# OBCv4_21.net
KiCad netlist of a schematic drawn in EAGLE
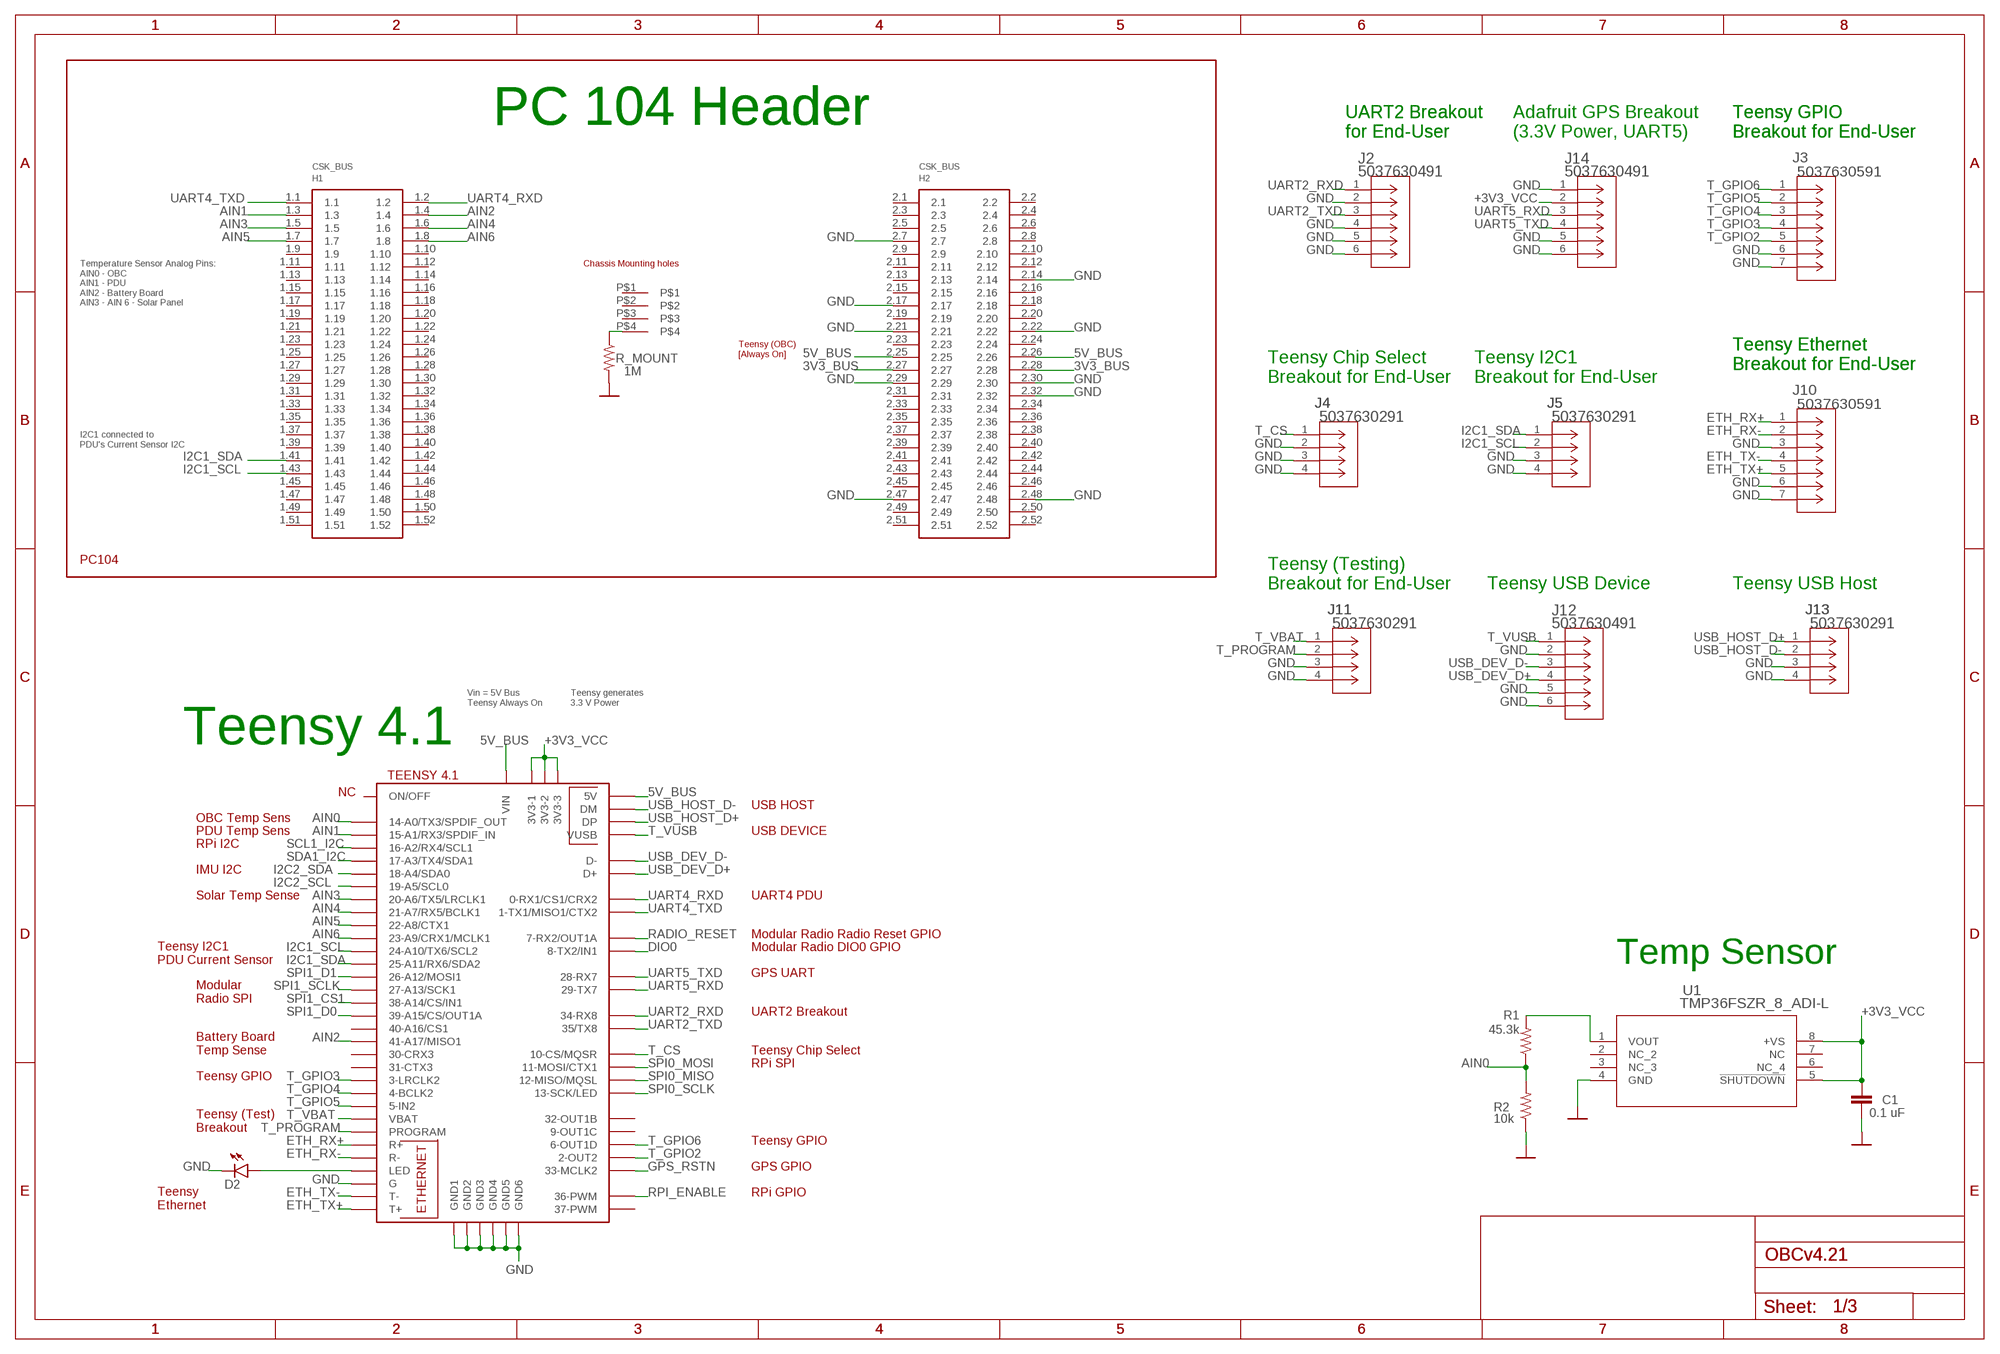
[diagram p0: schematic, sheet 1]
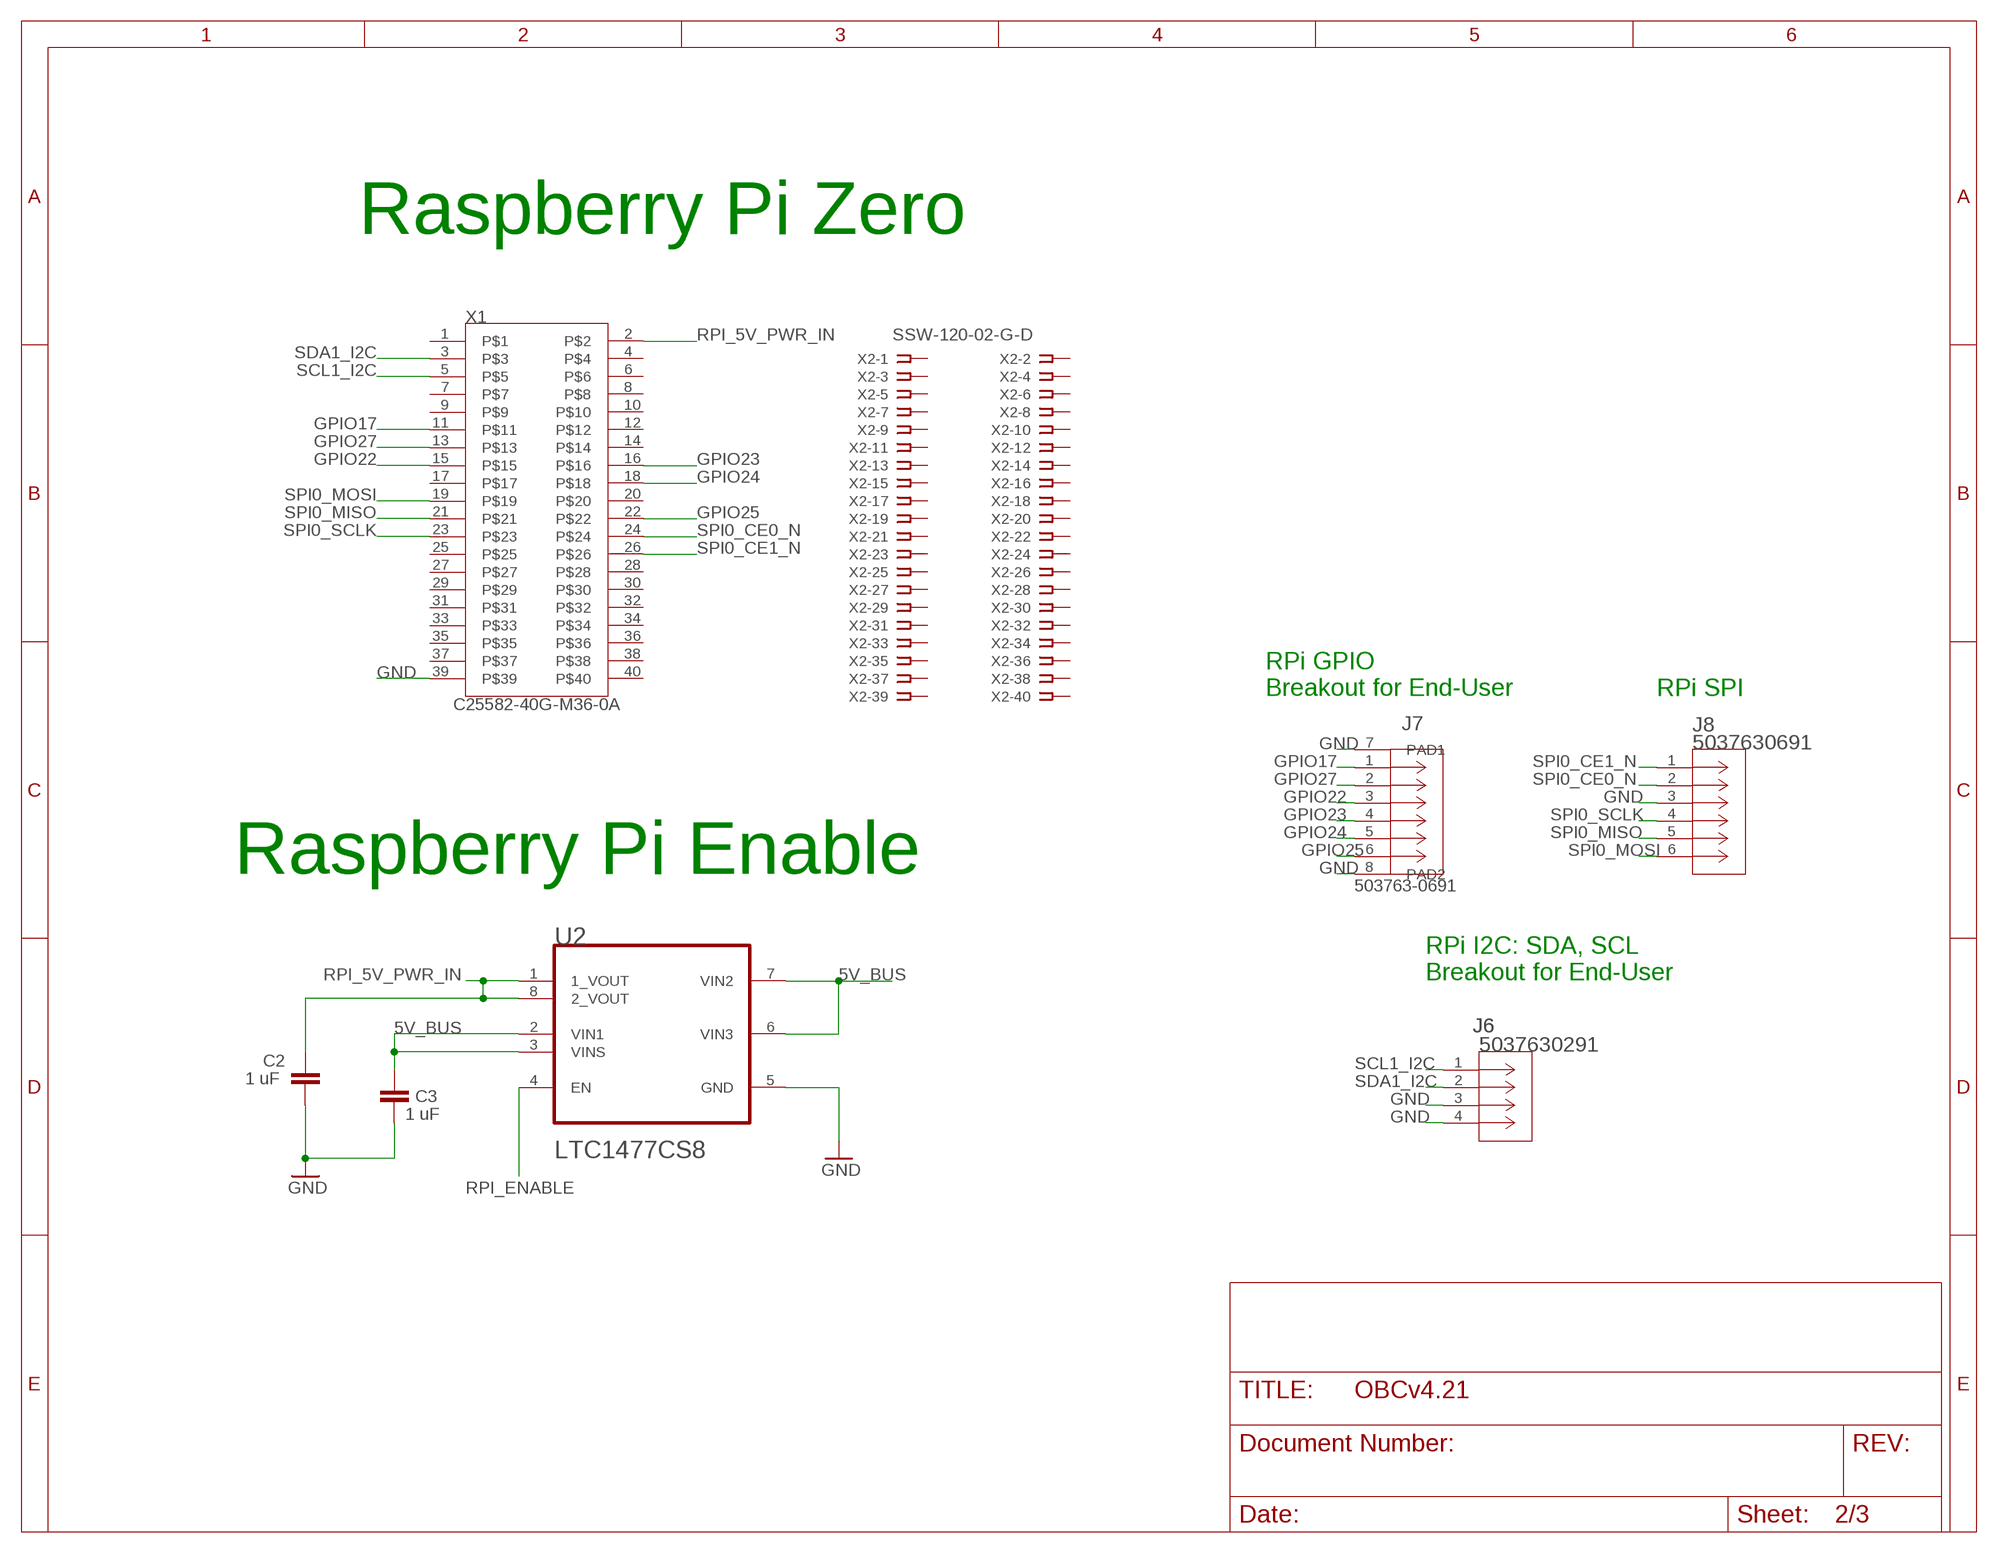
[diagram p1: schematic, sheet 2]
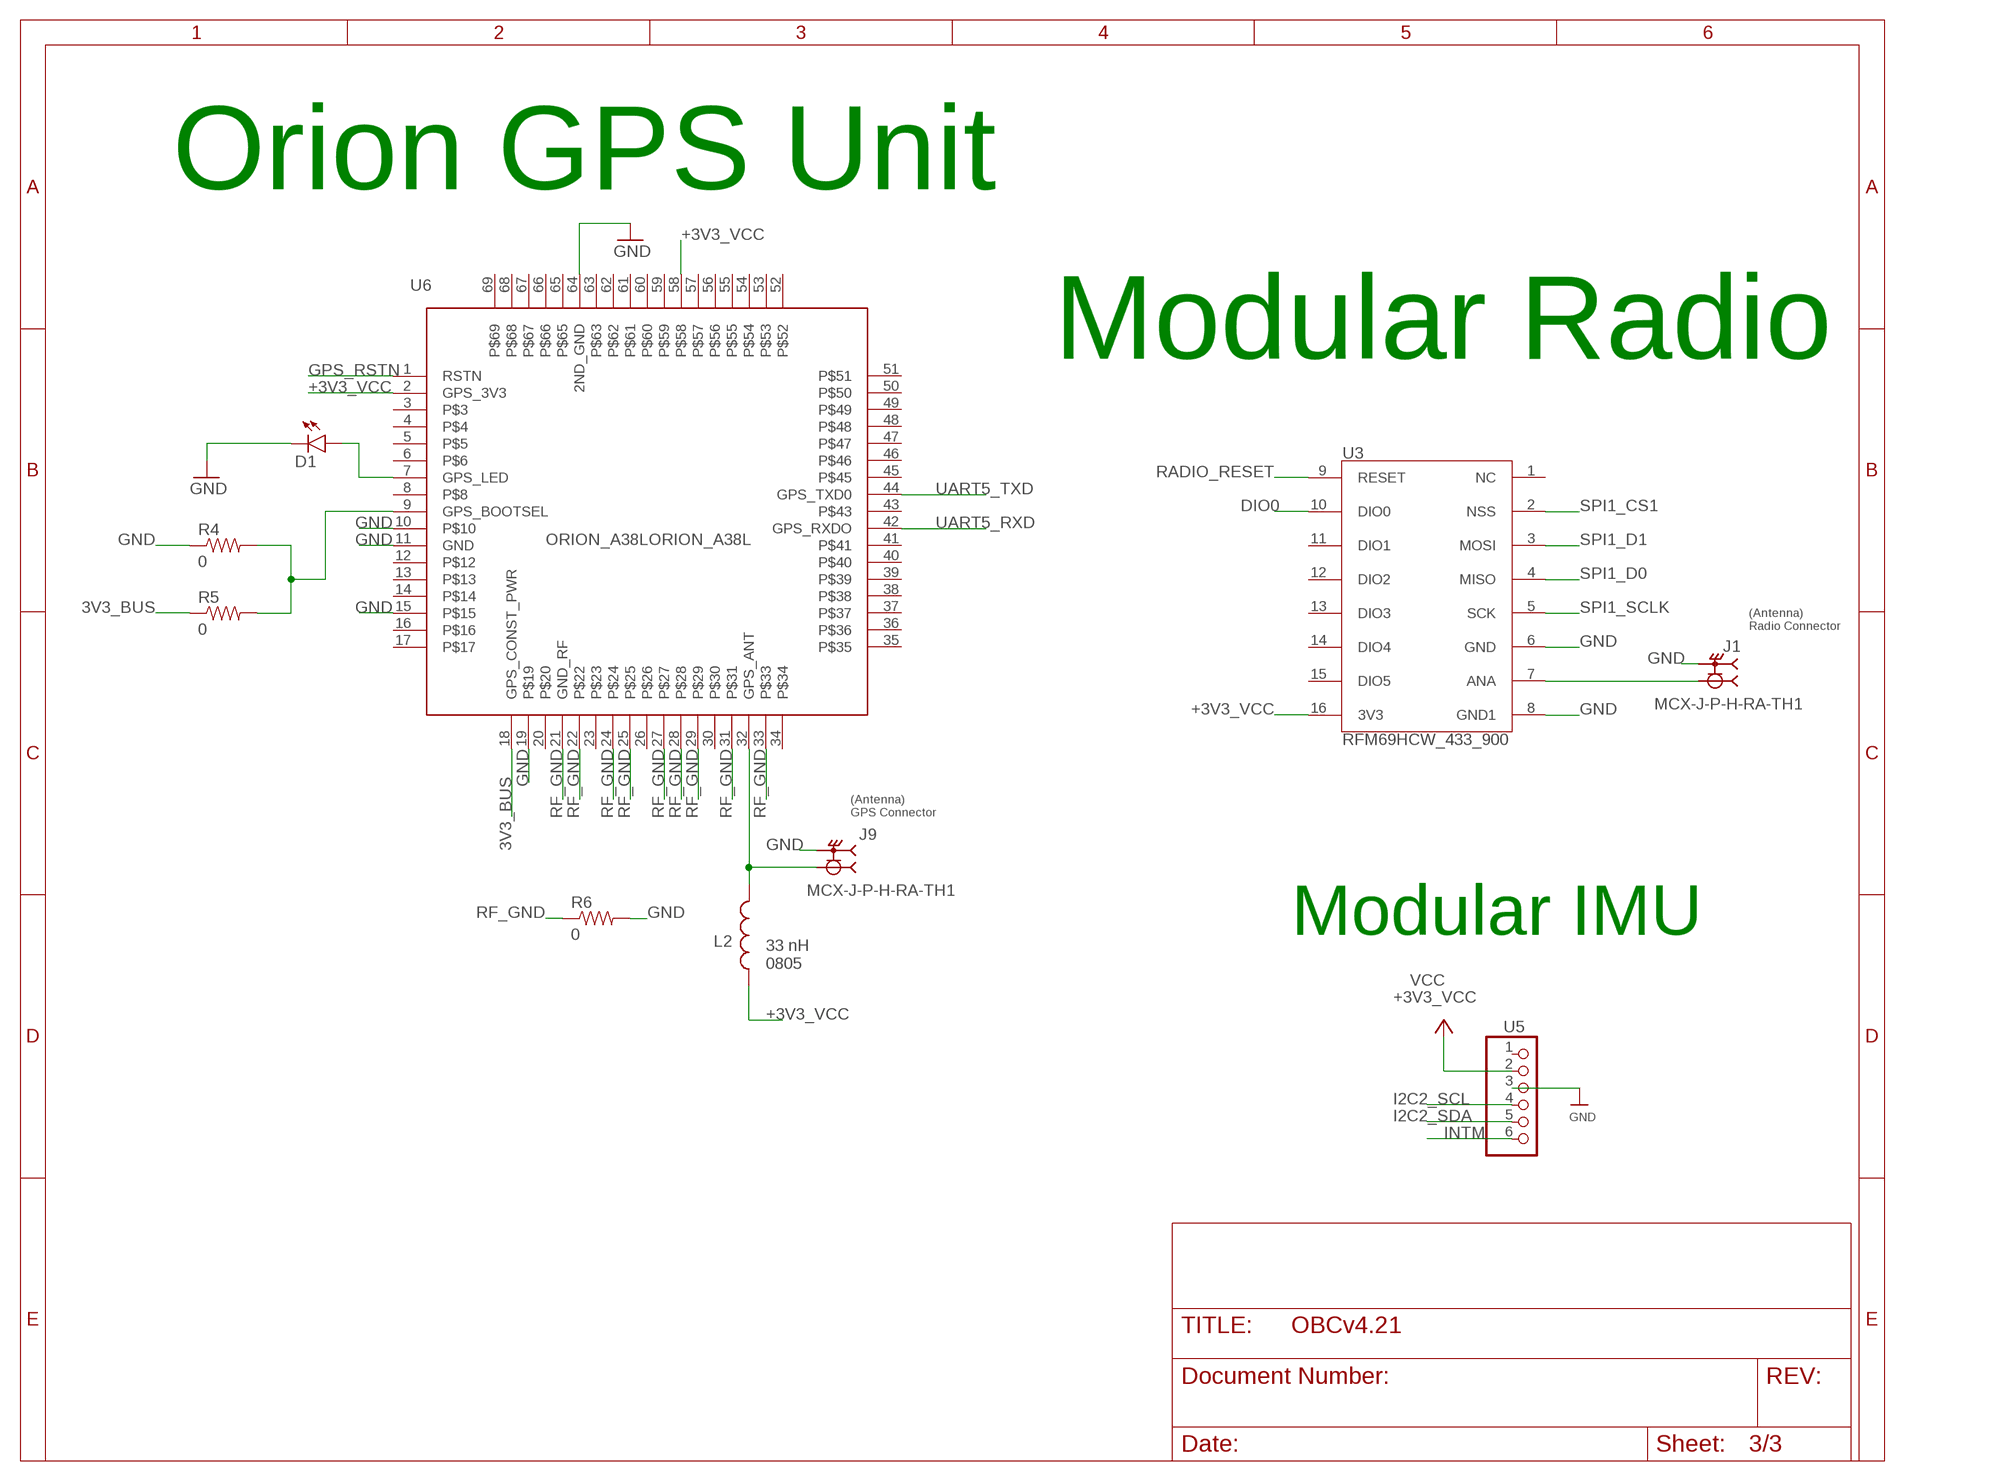
[diagram p2: schematic, sheet 3]

(export (version "E")
  (design (tool "Eeschema 10.0.6"))
  (components
    (comp (ref "C2")
      (value "1 uF")
      (footprint "eagle-import:0805")
      (libsource (lib "eagle-import") (part "CAP0805"))
    )
    (comp (ref "C3")
      (value "1 uF")
      (footprint "eagle-import:0805")
      (libsource (lib "eagle-import") (part "CAP0805"))
    )
    (comp (ref "J6")
      (value "5037630291")
      (footprint "eagle-import:CON_5037630291")
      (fields (field (name "COPYRIGHT") "Copyright (C) 2018 Accelerated Designs. All rights reserved"))
      (libsource (lib "eagle-import") (part "5037630291"))
    )
    (comp (ref "J7")
      (value "503763-0691")
      (footprint "eagle-import:CONN_503763-0691_MOL")
      (fields (field (name "COPYRIGHT") "Copyright (C) 2018 Accelerated Designs. All rights reserved"))
      (libsource (lib "eagle-import") (part "503763-0691"))
    )
    (comp (ref "J8")
      (value "5037630691")
      (footprint "eagle-import:CONN_503763-0691_MOL")
      (fields
        (field (name "MANUFACTURER_PART_NUMBER") "503763-0691")
        (field (name "COPYRIGHT") "Copyright (C) 2018 Accelerated Designs. All rights reserved")
      )
      (libsource (lib "eagle-import") (part "5037630691"))
    )
    (comp (ref "U2")
      (value "LTC1477CS8LINEAR_TECHNOLOGY_LTC1477CS8_0_2")
      (footprint "eagle-import:LINEAR_TECHNOLOGY_LTC1477CS8_2")
      (fields (field (name "MF") "Linear Technology") (field (name "MPN") "LTC1477CS8"))
      (libsource (lib "eagle-import") (part "LTC1477CS8LINEAR_TECHNOLOGY_LTC1477CS8_0_2"))
    )
    (comp (ref "X1")
      (value "C25582-40G-M36-0A")
      (footprint "eagle-import:ADAFRUIT_C25582-40G-M36-0A_0")
      (libsource (lib "eagle-import") (part "C25582-40G-M36-0A"))
    )
    (comp (ref "X2")
      (value "SSW-120-02-G-D")
      (footprint "eagle-import:SSW-120-02-G-D")
      (fields (field (name "MF") "Samtec Inc."))
      (libsource (lib "eagle-import") (part "SSW-120-02-G-D"))
    )
    (comp (ref "C1")
      (value "0.1 uF")
      (footprint "eagle-import:0805")
      (libsource (lib "eagle-import") (part "CAP0805"))
    )
    (comp (ref "D2")
      (value "LEDCHIP-LED0603")
      (footprint "eagle-import:CHIP-LED0603")
      (libsource (lib "eagle-import") (part "LEDCHIP-LED0603"))
    )
    (comp (ref "H1")
      (value "PC104_WCONN")
      (footprint "eagle-import:PC104_WCONN")
      (libsource (lib "eagle-import") (part "PC104_WCONN"))
    )
    (comp (ref "J2")
      (value "5037630491")
      (footprint "eagle-import:CON_5037630491")
      (fields (field (name "COPYRIGHT") "Copyright (C) 2018 Accelerated Designs. All rights reserved"))
      (libsource (lib "eagle-import") (part "5037630491"))
    )
    (comp (ref "J3")
      (value "5037630591")
      (footprint "eagle-import:CON_5037630591")
      (fields (field (name "COPYRIGHT") "Copyright (C) 2021 Ultra Librarian. All rights reserved."))
      (libsource (lib "eagle-import") (part "5037630591"))
    )
    (comp (ref "J4")
      (value "5037630291")
      (footprint "eagle-import:CON_5037630291")
      (fields (field (name "COPYRIGHT") "Copyright (C) 2018 Accelerated Designs. All rights reserved"))
      (libsource (lib "eagle-import") (part "5037630291"))
    )
    (comp (ref "J5")
      (value "5037630291")
      (footprint "eagle-import:CON_5037630291")
      (fields (field (name "COPYRIGHT") "Copyright (C) 2018 Accelerated Designs. All rights reserved"))
      (libsource (lib "eagle-import") (part "5037630291"))
    )
    (comp (ref "J10")
      (value "5037630591")
      (footprint "eagle-import:CON_5037630591")
      (fields (field (name "COPYRIGHT") "Copyright (C) 2021 Ultra Librarian. All rights reserved."))
      (libsource (lib "eagle-import") (part "5037630591"))
    )
    (comp (ref "J11")
      (value "5037630291")
      (footprint "eagle-import:CON_5037630291")
      (fields (field (name "COPYRIGHT") "Copyright (C) 2018 Accelerated Designs. All rights reserved"))
      (libsource (lib "eagle-import") (part "5037630291"))
    )
    (comp (ref "J12")
      (value "5037630491")
      (footprint "eagle-import:CON_5037630491")
      (fields (field (name "COPYRIGHT") "Copyright (C) 2018 Accelerated Designs. All rights reserved"))
      (libsource (lib "eagle-import") (part "5037630491"))
    )
    (comp (ref "J13")
      (value "5037630291")
      (footprint "eagle-import:CON_5037630291")
      (fields (field (name "COPYRIGHT") "Copyright (C) 2018 Accelerated Designs. All rights reserved"))
      (libsource (lib "eagle-import") (part "5037630291"))
    )
    (comp (ref "J14")
      (value "5037630491")
      (footprint "eagle-import:CON_5037630491")
      (fields (field (name "COPYRIGHT") "Copyright (C) 2018 Accelerated Designs. All rights reserved"))
      (libsource (lib "eagle-import") (part "5037630491"))
    )
    (comp (ref "R1")
      (value "45.3k")
      (footprint "eagle-import:0805")
      (libsource (lib "eagle-import") (part "RESISTOR0805-RES"))
    )
    (comp (ref "R2")
      (value "10k")
      (footprint "eagle-import:0805")
      (libsource (lib "eagle-import") (part "RESISTOR0805-RES"))
    )
    (comp (ref "R_MOUNT")
      (value "1M")
      (footprint "eagle-import:0805")
      (libsource (lib "eagle-import") (part "RESISTOR0805-RES"))
    )
    (comp (ref "U$1")
      (value "TEENSY41")
      (footprint "eagle-import:TEENSY41")
      (libsource (lib "eagle-import") (part "TEENSY41"))
    )
    (comp (ref "U1")
      (value "TMP36FSZR_8_ADI-L")
      (footprint "eagle-import:R_8_ADI-L")
      (fields
        (field (name "MANUFACTURER_PART_NUMBER") "TMP36FSZ")
        (field (name "COPYRIGHT") "Copyright (C) 2021 Ultra Librarian. All rights reserved.")
      )
      (libsource (lib "eagle-import") (part "TMP36FSZR_8_ADI-L"))
    )
    (comp (ref "D1")
      (value "LEDCHIP-LED0603")
      (footprint "eagle-import:CHIP-LED0603")
      (libsource (lib "eagle-import") (part "LEDCHIP-LED0603"))
    )
    (comp (ref "J1")
      (value "MCX-J-P-H-RA-TH1")
      (footprint "eagle-import:SAMTEC_MCX-J-P-H-RA-TH1")
      (fields (field (name "DIGI-KEY_PART_NUMBER") "SAM10607-ND") (field (name "MF") "Samtec"))
      (libsource (lib "eagle-import") (part "MCX-J-P-H-RA-TH1"))
    )
    (comp (ref "J9")
      (value "MCX-J-P-H-RA-TH1")
      (footprint "eagle-import:SAMTEC_MCX-J-P-H-RA-TH1")
      (fields (field (name "DIGI-KEY_PART_NUMBER") "SAM10607-ND") (field (name "MF") "Samtec"))
      (libsource (lib "eagle-import") (part "MCX-J-P-H-RA-TH1"))
    )
    (comp (ref "L2")
      (value "AIMC-0805-2N2S-T")
      (footprint "eagle-import:INDC2012X105N")
      (fields (field (name "DIGI-KEY_PART_NUMBER") "535-11562-1-ND") (field (name "MF") "Abracon"))
      (libsource (lib "eagle-import") (part "AIMC-0805-2N2S-T"))
    )
    (comp (ref "R4")
      (value "0")
      (footprint "eagle-import:0805")
      (libsource (lib "eagle-import") (part "RESISTOR0805-RES"))
    )
    (comp (ref "R5")
      (value "0")
      (footprint "eagle-import:0805")
      (libsource (lib "eagle-import") (part "RESISTOR0805-RES"))
    )
    (comp (ref "R6")
      (value "0")
      (footprint "eagle-import:0805")
      (libsource (lib "eagle-import") (part "RESISTOR0805-RES"))
    )
    (comp (ref "U3")
      (value "RFM69HCW_433_900")
      (footprint "eagle-import:RFM69HCW_433")
      (libsource (lib "eagle-import") (part "RFM69HCW_433_900"))
    )
    (comp (ref "U5")
      (value "HEADER-1X670MIL")
      (footprint "eagle-import:1X06_ROUND_70")
      (libsource (lib "eagle-import") (part "HEADER-1X670MIL"))
    )
    (comp (ref "U6")
      (value "ORION_A38LORION_A38L")
      (footprint "eagle-import:ORION_A38L")
      (libsource (lib "eagle-import") (part "ORION_A38LORION_A38L"))
    )
  )
  (nets
    (net (code "1") (name "+3V3_VCC") (class "Default")
      (node (ref "C1") (pin "1") (pinfunction "1_1") (pintype "passive"))
      (node (ref "J14") (pin "2") (pinfunction "2_2") (pintype "passive"))
      (node (ref "L2") (pin "1") (pinfunction "1_1") (pintype "passive"))
      (node (ref "U$1") (pin "3V3-1") (pinfunction "3V3-1_3V3-1") (pintype "bidirectional"))
      (node (ref "U$1") (pin "3V3-2") (pinfunction "3V3-2_3V3-2") (pintype "bidirectional"))
      (node (ref "U$1") (pin "3V3-3") (pinfunction "3V3-3_3V3-3") (pintype "bidirectional"))
      (node (ref "U1") (pin "5") (pinfunction "~{SHUTDOWN}_5") (pintype "passive"))
      (node (ref "U1") (pin "8") (pinfunction "+VS_8") (pintype "power_in"))
      (node (ref "U3") (pin "16") (pinfunction "3V3_16") (pintype "bidirectional"))
      (node (ref "U5") (pin "2") (pinfunction "2_2") (pintype "passive"))
      (node (ref "U6") (pin "2") (pinfunction "GPS_3V3_2") (pintype "bidirectional"))
      (node (ref "U6") (pin "58") (pinfunction "P$58_58") (pintype "bidirectional"))
    )
    (net (code "2") (name "3V3_BUS") (class "Default")
      (node (ref "H1") (pin "2.27") (pinfunction "2.27_2.27") (pintype "bidirectional"))
      (node (ref "H1") (pin "2.28") (pinfunction "2.28_2.28") (pintype "bidirectional"))
      (node (ref "R5") (pin "1") (pinfunction "1_1") (pintype "passive"))
      (node (ref "U6") (pin "18") (pinfunction "GPS_CONST_PWR_18") (pintype "bidirectional"))
    )
    (net (code "3") (name "5V_BUS") (class "Default")
      (node (ref "C3") (pin "1") (pinfunction "1_1") (pintype "passive"))
      (node (ref "H1") (pin "2.25") (pinfunction "2.25_2.25") (pintype "bidirectional"))
      (node (ref "H1") (pin "2.26") (pinfunction "2.26_2.26") (pintype "bidirectional"))
      (node (ref "U$1") (pin "+5V") (pinfunction "5V_+5V") (pintype "bidirectional"))
      (node (ref "U$1") (pin "VIN") (pinfunction "VIN_VIN") (pintype "bidirectional"))
      (node (ref "U2") (pin "2") (pinfunction "VIN1_2") (pintype "power_in"))
      (node (ref "U2") (pin "3") (pinfunction "VINS_3") (pintype "power_in"))
      (node (ref "U2") (pin "6") (pinfunction "VIN3_6") (pintype "power_in"))
      (node (ref "U2") (pin "7") (pinfunction "VIN2_7") (pintype "power_in"))
    )
    (net (code "4") (name "AIN0") (class "Default")
      (node (ref "R1") (pin "1") (pinfunction "1_1") (pintype "passive"))
      (node (ref "R2") (pin "2") (pinfunction "2_2") (pintype "passive"))
      (node (ref "U$1") (pin "14-A0/TX3/SPDIF_OUT") (pinfunction "14-A0/TX3/SPDIF_OUT_14-A0/TX3/SPDIF_OUT") (pintype "bidirectional"))
    )
    (net (code "5") (name "AIN1") (class "Default")
      (node (ref "H1") (pin "1.3") (pinfunction "1.3_1.3") (pintype "bidirectional"))
      (node (ref "U$1") (pin "15-A1/RX3/SPDIF_IN") (pinfunction "15-A1/RX3/SPDIF_IN_15-A1/RX3/SPDIF_IN") (pintype "bidirectional"))
    )
    (net (code "6") (name "AIN2") (class "Default")
      (node (ref "H1") (pin "1.4") (pinfunction "1.4_1.4") (pintype "bidirectional"))
      (node (ref "U$1") (pin "41-A17/MISO1") (pinfunction "41-A17/MISO1_41-A17/MISO1") (pintype "bidirectional"))
    )
    (net (code "7") (name "AIN3") (class "Default")
      (node (ref "H1") (pin "1.5") (pinfunction "1.5_1.5") (pintype "bidirectional"))
      (node (ref "U$1") (pin "20-A6/TX5/LRCLK1") (pinfunction "20-A6/TX5/LRCLK1_20-A6/TX5/LRCLK1") (pintype "bidirectional"))
    )
    (net (code "8") (name "AIN4") (class "Default")
      (node (ref "H1") (pin "1.6") (pinfunction "1.6_1.6") (pintype "bidirectional"))
      (node (ref "U$1") (pin "21-A7/RX5/BCLK1") (pinfunction "21-A7/RX5/BCLK1_21-A7/RX5/BCLK1") (pintype "bidirectional"))
    )
    (net (code "9") (name "AIN5") (class "Default")
      (node (ref "H1") (pin "1.7") (pinfunction "1.7_1.7") (pintype "bidirectional"))
      (node (ref "U$1") (pin "22-A8/CTX1") (pinfunction "22-A8/CTX1_22-A8/CTX1") (pintype "bidirectional"))
    )
    (net (code "10") (name "AIN6") (class "Default")
      (node (ref "H1") (pin "1.8") (pinfunction "1.8_1.8") (pintype "bidirectional"))
      (node (ref "U$1") (pin "23-A9/CRX1/MCLK1") (pinfunction "23-A9/CRX1/MCLK1_23-A9/CRX1/MCLK1") (pintype "bidirectional"))
    )
    (net (code "11") (name "DIO0") (class "Default")
      (node (ref "U$1") (pin "8-TX2/IN1") (pinfunction "8-TX2/IN1_8-TX2/IN1") (pintype "bidirectional"))
      (node (ref "U3") (pin "10") (pinfunction "DIO0_10") (pintype "bidirectional"))
    )
    (net (code "12") (name "ETH_RX+") (class "Default")
      (node (ref "J10") (pin "1") (pinfunction "1_1") (pintype "passive"))
      (node (ref "U$1") (pin "R+") (pinfunction "R+_R+") (pintype "bidirectional"))
    )
    (net (code "13") (name "ETH_RX-") (class "Default")
      (node (ref "J10") (pin "2") (pinfunction "2_2") (pintype "passive"))
      (node (ref "U$1") (pin "R-") (pinfunction "R-_R-") (pintype "bidirectional"))
    )
    (net (code "14") (name "ETH_TX+") (class "Default")
      (node (ref "J10") (pin "5") (pinfunction "5_5") (pintype "passive"))
      (node (ref "U$1") (pin "T+") (pinfunction "T+_T+") (pintype "bidirectional"))
    )
    (net (code "15") (name "ETH_TX-") (class "Default")
      (node (ref "J10") (pin "4") (pinfunction "4_4") (pintype "passive"))
      (node (ref "U$1") (pin "T-") (pinfunction "T-_T-") (pintype "bidirectional"))
    )
    (net (code "16") (name "GND") (class "Default")
      (node (ref "C1") (pin "2") (pinfunction "2_2") (pintype "passive"))
      (node (ref "C2") (pin "2") (pinfunction "2_2") (pintype "passive"))
      (node (ref "C3") (pin "2") (pinfunction "2_2") (pintype "passive"))
      (node (ref "D1") (pin "C") (pinfunction "C_C") (pintype "passive"))
      (node (ref "D2") (pin "C") (pinfunction "C_C") (pintype "passive"))
      (node (ref "H1") (pin "2.14") (pinfunction "2.14_2.14") (pintype "bidirectional"))
      (node (ref "H1") (pin "2.17") (pinfunction "2.17_2.17") (pintype "bidirectional"))
      (node (ref "H1") (pin "2.21") (pinfunction "2.21_2.21") (pintype "bidirectional"))
      (node (ref "H1") (pin "2.22") (pinfunction "2.22_2.22") (pintype "bidirectional"))
      (node (ref "H1") (pin "2.29") (pinfunction "2.29_2.29") (pintype "bidirectional"))
      (node (ref "H1") (pin "2.30") (pinfunction "2.30_2.30") (pintype "bidirectional"))
      (node (ref "H1") (pin "2.32") (pinfunction "2.32_2.32") (pintype "bidirectional"))
      (node (ref "H1") (pin "2.47") (pinfunction "2.47_2.47") (pintype "bidirectional"))
      (node (ref "H1") (pin "2.48") (pinfunction "2.48_2.48") (pintype "bidirectional"))
      (node (ref "H1") (pin "2.7") (pinfunction "2.7_2.7") (pintype "bidirectional"))
      (node (ref "J1") (pin "S1") (pinfunction "2_S1") (pintype "passive"))
      (node (ref "J1") (pin "S2") (pinfunction "2_S2") (pintype "passive"))
      (node (ref "J1") (pin "S3") (pinfunction "2_S3") (pintype "passive"))
      (node (ref "J1") (pin "S4") (pinfunction "2_S4") (pintype "passive"))
      (node (ref "J10") (pin "3") (pinfunction "3_3") (pintype "passive"))
      (node (ref "J10") (pin "6") (pinfunction "6_6") (pintype "passive"))
      (node (ref "J10") (pin "7") (pinfunction "7_7") (pintype "passive"))
      (node (ref "J11") (pin "3") (pinfunction "3_3") (pintype "passive"))
      (node (ref "J11") (pin "4") (pinfunction "4_4") (pintype "passive"))
      (node (ref "J12") (pin "2") (pinfunction "2_2") (pintype "passive"))
      (node (ref "J12") (pin "5") (pinfunction "5_5") (pintype "passive"))
      (node (ref "J12") (pin "6") (pinfunction "6_6") (pintype "passive"))
      (node (ref "J13") (pin "3") (pinfunction "3_3") (pintype "passive"))
      (node (ref "J13") (pin "4") (pinfunction "4_4") (pintype "passive"))
      (node (ref "J14") (pin "1") (pinfunction "1_1") (pintype "passive"))
      (node (ref "J14") (pin "5") (pinfunction "5_5") (pintype "passive"))
      (node (ref "J14") (pin "6") (pinfunction "6_6") (pintype "passive"))
      (node (ref "J2") (pin "2") (pinfunction "2_2") (pintype "passive"))
      (node (ref "J2") (pin "4") (pinfunction "4_4") (pintype "passive"))
      (node (ref "J2") (pin "5") (pinfunction "5_5") (pintype "passive"))
      (node (ref "J2") (pin "6") (pinfunction "6_6") (pintype "passive"))
      (node (ref "J3") (pin "6") (pinfunction "6_6") (pintype "passive"))
      (node (ref "J3") (pin "7") (pinfunction "7_7") (pintype "passive"))
      (node (ref "J4") (pin "2") (pinfunction "2_2") (pintype "passive"))
      (node (ref "J4") (pin "3") (pinfunction "3_3") (pintype "passive"))
      (node (ref "J4") (pin "4") (pinfunction "4_4") (pintype "passive"))
      (node (ref "J5") (pin "3") (pinfunction "3_3") (pintype "passive"))
      (node (ref "J5") (pin "4") (pinfunction "4_4") (pintype "passive"))
      (node (ref "J6") (pin "3") (pinfunction "3_3") (pintype "passive"))
      (node (ref "J6") (pin "4") (pinfunction "4_4") (pintype "passive"))
      (node (ref "J7") (pin "7") (pinfunction "PAD1_7") (pintype "bidirectional"))
      (node (ref "J7") (pin "8") (pinfunction "PAD2_8") (pintype "bidirectional"))
      (node (ref "J8") (pin "3") (pinfunction "3_3") (pintype "passive"))
      (node (ref "J9") (pin "S1") (pinfunction "2_S1") (pintype "passive"))
      (node (ref "J9") (pin "S2") (pinfunction "2_S2") (pintype "passive"))
      (node (ref "J9") (pin "S3") (pinfunction "2_S3") (pintype "passive"))
      (node (ref "J9") (pin "S4") (pinfunction "2_S4") (pintype "passive"))
      (node (ref "R2") (pin "1") (pinfunction "1_1") (pintype "passive"))
      (node (ref "R4") (pin "1") (pinfunction "1_1") (pintype "passive"))
      (node (ref "R6") (pin "2") (pinfunction "2_2") (pintype "passive"))
      (node (ref "R_MOUNT") (pin "2") (pinfunction "2_2") (pintype "passive"))
      (node (ref "U$1") (pin "G") (pinfunction "G_G") (pintype "bidirectional"))
      (node (ref "U$1") (pin "GND1") (pinfunction "GND1_GND1") (pintype "bidirectional"))
      (node (ref "U$1") (pin "GND2") (pinfunction "GND2_GND2") (pintype "bidirectional"))
      (node (ref "U$1") (pin "GND3") (pinfunction "GND3_GND3") (pintype "bidirectional"))
      (node (ref "U$1") (pin "GND4") (pinfunction "GND4_GND4") (pintype "bidirectional"))
      (node (ref "U$1") (pin "GND5") (pinfunction "GND5_GND5") (pintype "bidirectional"))
      (node (ref "U$1") (pin "GND6") (pinfunction "GND6_GND6") (pintype "bidirectional"))
      (node (ref "U1") (pin "4") (pinfunction "GND_4") (pintype "passive"))
      (node (ref "U2") (pin "5") (pinfunction "GND_5") (pintype "power_in"))
      (node (ref "U3") (pin "6") (pinfunction "GND_6") (pintype "bidirectional"))
      (node (ref "U3") (pin "8") (pinfunction "GND1_8") (pintype "bidirectional"))
      (node (ref "U5") (pin "3") (pinfunction "3_3") (pintype "passive"))
      (node (ref "U6") (pin "10") (pinfunction "P$10_10") (pintype "bidirectional"))
      (node (ref "U6") (pin "11") (pinfunction "GND_11") (pintype "bidirectional"))
      (node (ref "U6") (pin "15") (pinfunction "P$15_15") (pintype "bidirectional"))
      (node (ref "U6") (pin "19") (pinfunction "P$19_19") (pintype "bidirectional"))
      (node (ref "U6") (pin "64") (pinfunction "2ND_GND_64") (pintype "bidirectional"))
      (node (ref "X1") (pin "39") (pinfunction "P$39_39") (pintype "bidirectional"))
    )
    (net (code "17") (name "GPIO17") (class "Default")
      (node (ref "J7") (pin "1") (pinfunction "1_1") (pintype "passive"))
      (node (ref "X1") (pin "11") (pinfunction "P$11_11") (pintype "bidirectional"))
    )
    (net (code "18") (name "GPIO22") (class "Default")
      (node (ref "J7") (pin "3") (pinfunction "3_3") (pintype "passive"))
      (node (ref "X1") (pin "15") (pinfunction "P$15_15") (pintype "bidirectional"))
    )
    (net (code "19") (name "GPIO23") (class "Default")
      (node (ref "J7") (pin "4") (pinfunction "4_4") (pintype "passive"))
      (node (ref "X1") (pin "16") (pinfunction "P$16_16") (pintype "bidirectional"))
    )
    (net (code "20") (name "GPIO24") (class "Default")
      (node (ref "J7") (pin "5") (pinfunction "5_5") (pintype "passive"))
      (node (ref "X1") (pin "18") (pinfunction "P$18_18") (pintype "bidirectional"))
    )
    (net (code "21") (name "GPIO25") (class "Default")
      (node (ref "J7") (pin "6") (pinfunction "6_6") (pintype "passive"))
      (node (ref "X1") (pin "22") (pinfunction "P$22_22") (pintype "bidirectional"))
    )
    (net (code "22") (name "GPIO27") (class "Default")
      (node (ref "J7") (pin "2") (pinfunction "2_2") (pintype "passive"))
      (node (ref "X1") (pin "13") (pinfunction "P$13_13") (pintype "bidirectional"))
    )
    (net (code "23") (name "GPS_RSTN") (class "Default")
      (node (ref "U$1") (pin "33-MCLK2") (pinfunction "33-MCLK2_33-MCLK2") (pintype "bidirectional"))
      (node (ref "U6") (pin "1") (pinfunction "RSTN_1") (pintype "bidirectional"))
    )
    (net (code "24") (name "I2C1_SCL") (class "Default")
      (node (ref "H1") (pin "1.43") (pinfunction "1.43_1.43") (pintype "bidirectional"))
      (node (ref "J5") (pin "2") (pinfunction "2_2") (pintype "passive"))
      (node (ref "U$1") (pin "24-A10/TX6/SCL2") (pinfunction "24-A10/TX6/SCL2_24-A10/TX6/SCL2") (pintype "bidirectional"))
    )
    (net (code "25") (name "I2C1_SDA") (class "Default")
      (node (ref "H1") (pin "1.41") (pinfunction "1.41_1.41") (pintype "bidirectional"))
      (node (ref "J5") (pin "1") (pinfunction "1_1") (pintype "passive"))
      (node (ref "U$1") (pin "25-A11/RX6/SDA2") (pinfunction "25-A11/RX6/SDA2_25-A11/RX6/SDA2") (pintype "bidirectional"))
    )
    (net (code "26") (name "I2C2_SCL") (class "Default")
      (node (ref "U$1") (pin "19-A5/SCL0") (pinfunction "19-A5/SCL0_19-A5/SCL0") (pintype "bidirectional"))
      (node (ref "U5") (pin "4") (pinfunction "4_4") (pintype "passive"))
    )
    (net (code "27") (name "I2C2_SDA") (class "Default")
      (node (ref "U$1") (pin "18-A4/SDA0") (pinfunction "18-A4/SDA0_18-A4/SDA0") (pintype "bidirectional"))
      (node (ref "U5") (pin "5") (pinfunction "5_5") (pintype "passive"))
    )
    (net (code "28") (name "INTM") (class "Default")
      (node (ref "U5") (pin "6") (pinfunction "6_6") (pintype "passive"))
    )
    (net (code "29") (name "Net-(D2-PadA)") (class "Default")
      (node (ref "D2") (pin "A") (pinfunction "A_A") (pintype "passive"))
      (node (ref "U$1") (pin "LED") (pinfunction "LED_LED") (pintype "bidirectional"))
    )
    (net (code "30") (name "Net-(H1-PadP$4)") (class "Default")
      (node (ref "H1") (pin "P$4") (pinfunction "P$4_P$4") (pintype "bidirectional"))
      (node (ref "R_MOUNT") (pin "1") (pinfunction "1_1") (pintype "passive"))
    )
    (net (code "31") (name "Net-(U1-VOUT)") (class "Default")
      (node (ref "R1") (pin "2") (pinfunction "2_2") (pintype "passive"))
      (node (ref "U1") (pin "1") (pinfunction "VOUT_1") (pintype "output"))
    )
    (net (code "32") (name "Net-(U3-ANA)") (class "Default")
      (node (ref "J1") (pin "1") (pinfunction "1_1") (pintype "passive"))
      (node (ref "U3") (pin "7") (pinfunction "ANA_7") (pintype "bidirectional"))
    )
    (net (code "33") (name "Net-(U6-GPS_ANT)") (class "Default")
      (node (ref "J9") (pin "1") (pinfunction "1_1") (pintype "passive"))
      (node (ref "L2") (pin "2") (pinfunction "2_2") (pintype "passive"))
      (node (ref "U6") (pin "32") (pinfunction "GPS_ANT_32") (pintype "bidirectional"))
    )
    (net (code "34") (name "Net-(U6-GPS_BOOTSEL)") (class "Default")
      (node (ref "R4") (pin "2") (pinfunction "2_2") (pintype "passive"))
      (node (ref "R5") (pin "2") (pinfunction "2_2") (pintype "passive"))
      (node (ref "U6") (pin "9") (pinfunction "GPS_BOOTSEL_9") (pintype "bidirectional"))
    )
    (net (code "35") (name "Net-(U6-GPS_LED)") (class "Default")
      (node (ref "D1") (pin "A") (pinfunction "A_A") (pintype "passive"))
      (node (ref "U6") (pin "7") (pinfunction "GPS_LED_7") (pintype "bidirectional"))
    )
    (net (code "36") (name "RADIO_RESET") (class "Default")
      (node (ref "U$1") (pin "7-RX2/OUT1A") (pinfunction "7-RX2/OUT1A_7-RX2/OUT1A") (pintype "bidirectional"))
      (node (ref "U3") (pin "9") (pinfunction "RESET_9") (pintype "bidirectional"))
    )
    (net (code "37") (name "RF_GND") (class "Default")
      (node (ref "R6") (pin "1") (pinfunction "1_1") (pintype "passive"))
      (node (ref "U6") (pin "21") (pinfunction "GND_RF_21") (pintype "bidirectional"))
      (node (ref "U6") (pin "22") (pinfunction "P$22_22") (pintype "bidirectional"))
      (node (ref "U6") (pin "24") (pinfunction "P$24_24") (pintype "bidirectional"))
      (node (ref "U6") (pin "25") (pinfunction "P$25_25") (pintype "bidirectional"))
      (node (ref "U6") (pin "27") (pinfunction "P$27_27") (pintype "bidirectional"))
      (node (ref "U6") (pin "28") (pinfunction "P$28_28") (pintype "bidirectional"))
      (node (ref "U6") (pin "29") (pinfunction "P$29_29") (pintype "bidirectional"))
      (node (ref "U6") (pin "31") (pinfunction "P$31_31") (pintype "bidirectional"))
      (node (ref "U6") (pin "33") (pinfunction "P$33_33") (pintype "bidirectional"))
    )
    (net (code "38") (name "RPI_5V_PWR_IN") (class "Default")
      (node (ref "C2") (pin "1") (pinfunction "1_1") (pintype "passive"))
      (node (ref "U2") (pin "1") (pinfunction "1_VOUT_1") (pintype "power_in"))
      (node (ref "U2") (pin "8") (pinfunction "2_VOUT_8") (pintype "power_in"))
      (node (ref "X1") (pin "2") (pinfunction "P$2_2") (pintype "bidirectional"))
    )
    (net (code "39") (name "RPI_ENABLE") (class "Default")
      (node (ref "U$1") (pin "36-PWM") (pinfunction "36-PWM_36-PWM") (pintype "bidirectional"))
      (node (ref "U2") (pin "4") (pinfunction "EN_4") (pintype "input"))
    )
    (net (code "40") (name "SCL1_I2C") (class "Default")
      (node (ref "J6") (pin "1") (pinfunction "1_1") (pintype "passive"))
      (node (ref "U$1") (pin "16-A2/RX4/SCL1") (pinfunction "16-A2/RX4/SCL1_16-A2/RX4/SCL1") (pintype "bidirectional"))
      (node (ref "X1") (pin "5") (pinfunction "P$5_5") (pintype "bidirectional"))
    )
    (net (code "41") (name "SDA1_I2C") (class "Default")
      (node (ref "J6") (pin "2") (pinfunction "2_2") (pintype "passive"))
      (node (ref "U$1") (pin "17-A3/TX4/SDA1") (pinfunction "17-A3/TX4/SDA1_17-A3/TX4/SDA1") (pintype "bidirectional"))
      (node (ref "X1") (pin "3") (pinfunction "P$3_3") (pintype "bidirectional"))
    )
    (net (code "42") (name "SPI0_CE0_N") (class "Default")
      (node (ref "J8") (pin "2") (pinfunction "2_2") (pintype "passive"))
      (node (ref "X1") (pin "24") (pinfunction "P$24_24") (pintype "bidirectional"))
    )
    (net (code "43") (name "SPI0_CE1_N") (class "Default")
      (node (ref "J8") (pin "1") (pinfunction "1_1") (pintype "passive"))
      (node (ref "X1") (pin "26") (pinfunction "P$26_26") (pintype "bidirectional"))
    )
    (net (code "44") (name "SPI0_MISO") (class "Default")
      (node (ref "J8") (pin "5") (pinfunction "5_5") (pintype "passive"))
      (node (ref "U$1") (pin "12-MISO/MQSL") (pinfunction "12-MISO/MQSL_12-MISO/MQSL") (pintype "bidirectional"))
      (node (ref "X1") (pin "21") (pinfunction "P$21_21") (pintype "bidirectional"))
    )
    (net (code "45") (name "SPI0_MOSI") (class "Default")
      (node (ref "J8") (pin "6") (pinfunction "6_6") (pintype "passive"))
      (node (ref "U$1") (pin "11-MOSI/CTX1") (pinfunction "11-MOSI/CTX1_11-MOSI/CTX1") (pintype "bidirectional"))
      (node (ref "X1") (pin "19") (pinfunction "P$19_19") (pintype "bidirectional"))
    )
    (net (code "46") (name "SPI0_SCLK") (class "Default")
      (node (ref "J8") (pin "4") (pinfunction "4_4") (pintype "passive"))
      (node (ref "U$1") (pin "13-SCK/LED") (pinfunction "13-SCK/LED_13-SCK/LED") (pintype "bidirectional"))
      (node (ref "X1") (pin "23") (pinfunction "P$23_23") (pintype "bidirectional"))
    )
    (net (code "47") (name "SPI1_CS1") (class "Default")
      (node (ref "U$1") (pin "38-A14/CS/IN1") (pinfunction "38-A14/CS/IN1_38-A14/CS/IN1") (pintype "bidirectional"))
      (node (ref "U3") (pin "2") (pinfunction "NSS_2") (pintype "bidirectional"))
    )
    (net (code "48") (name "SPI1_D0") (class "Default")
      (node (ref "U$1") (pin "39-A15/CS/OUT1A") (pinfunction "39-A15/CS/OUT1A_39-A15/CS/OUT1A") (pintype "bidirectional"))
      (node (ref "U3") (pin "4") (pinfunction "MISO_4") (pintype "bidirectional"))
    )
    (net (code "49") (name "SPI1_D1") (class "Default")
      (node (ref "U$1") (pin "26-A12/MOSI1") (pinfunction "26-A12/MOSI1_26-A12/MOSI1") (pintype "bidirectional"))
      (node (ref "U3") (pin "3") (pinfunction "MOSI_3") (pintype "bidirectional"))
    )
    (net (code "50") (name "SPI1_SCLK") (class "Default")
      (node (ref "U$1") (pin "27-A13/SCK1") (pinfunction "27-A13/SCK1_27-A13/SCK1") (pintype "bidirectional"))
      (node (ref "U3") (pin "5") (pinfunction "SCK_5") (pintype "bidirectional"))
    )
    (net (code "51") (name "T_CS") (class "Default")
      (node (ref "J4") (pin "1") (pinfunction "1_1") (pintype "passive"))
      (node (ref "U$1") (pin "10-CS\\MQSR") (pinfunction "10-CS/MQSR_10-CS\\MQSR") (pintype "bidirectional"))
    )
    (net (code "52") (name "T_GPIO2") (class "Default")
      (node (ref "J3") (pin "5") (pinfunction "5_5") (pintype "passive"))
      (node (ref "U$1") (pin "2-OUT2") (pinfunction "2-OUT2_2-OUT2") (pintype "bidirectional"))
    )
    (net (code "53") (name "T_GPIO3") (class "Default")
      (node (ref "J3") (pin "4") (pinfunction "4_4") (pintype "passive"))
      (node (ref "U$1") (pin "3-LRCLK2") (pinfunction "3-LRCLK2_3-LRCLK2") (pintype "bidirectional"))
    )
    (net (code "54") (name "T_GPIO4") (class "Default")
      (node (ref "J3") (pin "3") (pinfunction "3_3") (pintype "passive"))
      (node (ref "U$1") (pin "4-BCLK2") (pinfunction "4-BCLK2_4-BCLK2") (pintype "bidirectional"))
    )
    (net (code "55") (name "T_GPIO5") (class "Default")
      (node (ref "J3") (pin "2") (pinfunction "2_2") (pintype "passive"))
      (node (ref "U$1") (pin "5-IN2") (pinfunction "5-IN2_5-IN2") (pintype "bidirectional"))
    )
    (net (code "56") (name "T_GPIO6") (class "Default")
      (node (ref "J3") (pin "1") (pinfunction "1_1") (pintype "passive"))
      (node (ref "U$1") (pin "6-OUT1D") (pinfunction "6-OUT1D_6-OUT1D") (pintype "bidirectional"))
    )
    (net (code "57") (name "T_PROGRAM") (class "Default")
      (node (ref "J11") (pin "2") (pinfunction "2_2") (pintype "passive"))
      (node (ref "U$1") (pin "PROGRAM") (pinfunction "PROGRAM_PROGRAM") (pintype "bidirectional"))
    )
    (net (code "58") (name "T_VBAT") (class "Default")
      (node (ref "J11") (pin "1") (pinfunction "1_1") (pintype "passive"))
      (node (ref "U$1") (pin "VBAT") (pinfunction "VBAT_VBAT") (pintype "bidirectional"))
    )
    (net (code "59") (name "T_VUSB") (class "Default")
      (node (ref "J12") (pin "1") (pinfunction "1_1") (pintype "passive"))
      (node (ref "U$1") (pin "VUSB") (pinfunction "VUSB_VUSB") (pintype "bidirectional"))
    )
    (net (code "60") (name "UART2_RXD") (class "Default")
      (node (ref "J2") (pin "1") (pinfunction "1_1") (pintype "passive"))
      (node (ref "U$1") (pin "34-RX8") (pinfunction "34-RX8_34-RX8") (pintype "bidirectional"))
    )
    (net (code "61") (name "UART2_TXD") (class "Default")
      (node (ref "J2") (pin "3") (pinfunction "3_3") (pintype "passive"))
      (node (ref "U$1") (pin "35-TX8") (pinfunction "35/TX8_35-TX8") (pintype "bidirectional"))
    )
    (net (code "62") (name "UART4_RXD") (class "Default")
      (node (ref "H1") (pin "1.2") (pinfunction "1.2_1.2") (pintype "bidirectional"))
      (node (ref "U$1") (pin "0-RX1/CS1/CRX2") (pinfunction "0-RX1/CS1/CRX2_0-RX1/CS1/CRX2") (pintype "bidirectional"))
    )
    (net (code "63") (name "UART4_TXD") (class "Default")
      (node (ref "H1") (pin "1.1") (pinfunction "1.1_1.1") (pintype "bidirectional"))
      (node (ref "U$1") (pin "1-TX1/MISO1/CTX2") (pinfunction "1-TX1/MISO1/CTX2_1-TX1/MISO1/CTX2") (pintype "bidirectional"))
    )
    (net (code "64") (name "UART5_RXD") (class "Default")
      (node (ref "J14") (pin "3") (pinfunction "3_3") (pintype "passive"))
      (node (ref "U$1") (pin "29-TX7") (pinfunction "29-TX7_29-TX7") (pintype "bidirectional"))
      (node (ref "U6") (pin "42") (pinfunction "GPS_RXDO_42") (pintype "input"))
    )
    (net (code "65") (name "UART5_TXD") (class "Default")
      (node (ref "J14") (pin "4") (pinfunction "4_4") (pintype "passive"))
      (node (ref "U$1") (pin "28-RX7") (pinfunction "28-RX7_28-RX7") (pintype "bidirectional"))
      (node (ref "U6") (pin "44") (pinfunction "GPS_TXD0_44") (pintype "output"))
    )
    (net (code "66") (name "USB_DEV_D+") (class "Default")
      (node (ref "J12") (pin "4") (pinfunction "4_4") (pintype "passive"))
      (node (ref "U$1") (pin "D+") (pinfunction "D+_D+") (pintype "bidirectional"))
    )
    (net (code "67") (name "USB_DEV_D-") (class "Default")
      (node (ref "J12") (pin "3") (pinfunction "3_3") (pintype "passive"))
      (node (ref "U$1") (pin "D-") (pinfunction "D-_D-") (pintype "bidirectional"))
    )
    (net (code "68") (name "USB_HOST_D+") (class "Default")
      (node (ref "J13") (pin "1") (pinfunction "1_1") (pintype "passive"))
      (node (ref "U$1") (pin "DP") (pinfunction "DP_DP") (pintype "bidirectional"))
    )
    (net (code "69") (name "USB_HOST_D-") (class "Default")
      (node (ref "J13") (pin "2") (pinfunction "2_2") (pintype "passive"))
      (node (ref "U$1") (pin "DM") (pinfunction "DM_DM") (pintype "bidirectional"))
    )
    (net (code "70") (name "unconnected-(H1-Pad1.9)") (class "Default")
      (node (ref "H1") (pin "1.9") (pinfunction "1.9_1.9") (pintype "bidirectional"))
    )
    (net (code "71") (name "unconnected-(H1-Pad1.10)") (class "Default")
      (node (ref "H1") (pin "1.10") (pinfunction "1.10_1.10") (pintype "bidirectional"))
    )
    (net (code "72") (name "unconnected-(H1-Pad1.11)") (class "Default")
      (node (ref "H1") (pin "1.11") (pinfunction "1.11_1.11") (pintype "bidirectional"))
    )
    (net (code "73") (name "unconnected-(H1-Pad1.12)") (class "Default")
      (node (ref "H1") (pin "1.12") (pinfunction "1.12_1.12") (pintype "bidirectional"))
    )
    (net (code "74") (name "unconnected-(H1-Pad1.13)") (class "Default")
      (node (ref "H1") (pin "1.13") (pinfunction "1.13_1.13") (pintype "bidirectional"))
    )
    (net (code "75") (name "unconnected-(H1-Pad1.14)") (class "Default")
      (node (ref "H1") (pin "1.14") (pinfunction "1.14_1.14") (pintype "bidirectional"))
    )
    (net (code "76") (name "unconnected-(H1-Pad1.15)") (class "Default")
      (node (ref "H1") (pin "1.15") (pinfunction "1.15_1.15") (pintype "bidirectional"))
    )
    (net (code "77") (name "unconnected-(H1-Pad1.16)") (class "Default")
      (node (ref "H1") (pin "1.16") (pinfunction "1.16_1.16") (pintype "bidirectional"))
    )
    (net (code "78") (name "unconnected-(H1-Pad1.17)") (class "Default")
      (node (ref "H1") (pin "1.17") (pinfunction "1.17_1.17") (pintype "bidirectional"))
    )
    (net (code "79") (name "unconnected-(H1-Pad1.18)") (class "Default")
      (node (ref "H1") (pin "1.18") (pinfunction "1.18_1.18") (pintype "bidirectional"))
    )
    (net (code "80") (name "unconnected-(H1-Pad1.19)") (class "Default")
      (node (ref "H1") (pin "1.19") (pinfunction "1.19_1.19") (pintype "bidirectional"))
    )
    (net (code "81") (name "unconnected-(H1-Pad1.20)") (class "Default")
      (node (ref "H1") (pin "1.20") (pinfunction "1.20_1.20") (pintype "bidirectional"))
    )
    (net (code "82") (name "unconnected-(H1-Pad1.21)") (class "Default")
      (node (ref "H1") (pin "1.21") (pinfunction "1.21_1.21") (pintype "bidirectional"))
    )
    (net (code "83") (name "unconnected-(H1-Pad1.22)") (class "Default")
      (node (ref "H1") (pin "1.22") (pinfunction "1.22_1.22") (pintype "bidirectional"))
    )
    (net (code "84") (name "unconnected-(H1-Pad1.23)") (class "Default")
      (node (ref "H1") (pin "1.23") (pinfunction "1.23_1.23") (pintype "bidirectional"))
    )
    (net (code "85") (name "unconnected-(H1-Pad1.24)") (class "Default")
      (node (ref "H1") (pin "1.24") (pinfunction "1.24_1.24") (pintype "bidirectional"))
    )
    (net (code "86") (name "unconnected-(H1-Pad1.25)") (class "Default")
      (node (ref "H1") (pin "1.25") (pinfunction "1.25_1.25") (pintype "bidirectional"))
    )
    (net (code "87") (name "unconnected-(H1-Pad1.26)") (class "Default")
      (node (ref "H1") (pin "1.26") (pinfunction "1.26_1.26") (pintype "bidirectional"))
    )
    (net (code "88") (name "unconnected-(H1-Pad1.27)") (class "Default")
      (node (ref "H1") (pin "1.27") (pinfunction "1.27_1.27") (pintype "bidirectional"))
    )
    (net (code "89") (name "unconnected-(H1-Pad1.28)") (class "Default")
      (node (ref "H1") (pin "1.28") (pinfunction "1.28_1.28") (pintype "bidirectional"))
    )
    (net (code "90") (name "unconnected-(H1-Pad1.29)") (class "Default")
      (node (ref "H1") (pin "1.29") (pinfunction "1.29_1.29") (pintype "bidirectional"))
    )
    (net (code "91") (name "unconnected-(H1-Pad1.30)") (class "Default")
      (node (ref "H1") (pin "1.30") (pinfunction "1.30_1.30") (pintype "bidirectional"))
    )
    (net (code "92") (name "unconnected-(H1-Pad1.31)") (class "Default")
      (node (ref "H1") (pin "1.31") (pinfunction "1.31_1.31") (pintype "bidirectional"))
    )
    (net (code "93") (name "unconnected-(H1-Pad1.32)") (class "Default")
      (node (ref "H1") (pin "1.32") (pinfunction "1.32_1.32") (pintype "bidirectional"))
    )
    (net (code "94") (name "unconnected-(H1-Pad1.33)") (class "Default")
      (node (ref "H1") (pin "1.33") (pinfunction "1.33_1.33") (pintype "bidirectional"))
    )
    (net (code "95") (name "unconnected-(H1-Pad1.34)") (class "Default")
      (node (ref "H1") (pin "1.34") (pinfunction "1.34_1.34") (pintype "bidirectional"))
    )
    (net (code "96") (name "unconnected-(H1-Pad1.35)") (class "Default")
      (node (ref "H1") (pin "1.35") (pinfunction "1.35_1.35") (pintype "bidirectional"))
    )
    (net (code "97") (name "unconnected-(H1-Pad1.36)") (class "Default")
      (node (ref "H1") (pin "1.36") (pinfunction "1.36_1.36") (pintype "bidirectional"))
    )
    (net (code "98") (name "unconnected-(H1-Pad1.37)") (class "Default")
      (node (ref "H1") (pin "1.37") (pinfunction "1.37_1.37") (pintype "bidirectional"))
    )
    (net (code "99") (name "unconnected-(H1-Pad1.38)") (class "Default")
      (node (ref "H1") (pin "1.38") (pinfunction "1.38_1.38") (pintype "bidirectional"))
    )
    (net (code "100") (name "unconnected-(H1-Pad1.39)") (class "Default")
      (node (ref "H1") (pin "1.39") (pinfunction "1.39_1.39") (pintype "bidirectional"))
    )
    (net (code "101") (name "unconnected-(H1-Pad1.40)") (class "Default")
      (node (ref "H1") (pin "1.40") (pinfunction "1.40_1.40") (pintype "bidirectional"))
    )
    (net (code "102") (name "unconnected-(H1-Pad1.42)") (class "Default")
      (node (ref "H1") (pin "1.42") (pinfunction "1.42_1.42") (pintype "bidirectional"))
    )
    (net (code "103") (name "unconnected-(H1-Pad1.44)") (class "Default")
      (node (ref "H1") (pin "1.44") (pinfunction "1.44_1.44") (pintype "bidirectional"))
    )
    (net (code "104") (name "unconnected-(H1-Pad1.45)") (class "Default")
      (node (ref "H1") (pin "1.45") (pinfunction "1.45_1.45") (pintype "bidirectional"))
    )
    (net (code "105") (name "unconnected-(H1-Pad1.46)") (class "Default")
      (node (ref "H1") (pin "1.46") (pinfunction "1.46_1.46") (pintype "bidirectional"))
    )
    (net (code "106") (name "unconnected-(H1-Pad1.47)") (class "Default")
      (node (ref "H1") (pin "1.47") (pinfunction "1.47_1.47") (pintype "bidirectional"))
    )
    (net (code "107") (name "unconnected-(H1-Pad1.48)") (class "Default")
      (node (ref "H1") (pin "1.48") (pinfunction "1.48_1.48") (pintype "bidirectional"))
    )
    (net (code "108") (name "unconnected-(H1-Pad1.49)") (class "Default")
      (node (ref "H1") (pin "1.49") (pinfunction "1.49_1.49") (pintype "bidirectional"))
    )
    (net (code "109") (name "unconnected-(H1-Pad1.50)") (class "Default")
      (node (ref "H1") (pin "1.50") (pinfunction "1.50_1.50") (pintype "bidirectional"))
    )
    (net (code "110") (name "unconnected-(H1-Pad1.51)") (class "Default")
      (node (ref "H1") (pin "1.51") (pinfunction "1.51_1.51") (pintype "bidirectional"))
    )
    (net (code "111") (name "unconnected-(H1-Pad1.52)") (class "Default")
      (node (ref "H1") (pin "1.52") (pinfunction "1.52_1.52") (pintype "bidirectional"))
    )
    (net (code "112") (name "unconnected-(H1-Pad2.1)") (class "Default")
      (node (ref "H1") (pin "2.1") (pinfunction "2.1_2.1") (pintype "bidirectional"))
    )
    (net (code "113") (name "unconnected-(H1-Pad2.2)") (class "Default")
      (node (ref "H1") (pin "2.2") (pinfunction "2.2_2.2") (pintype "bidirectional"))
    )
    (net (code "114") (name "unconnected-(H1-Pad2.3)") (class "Default")
      (node (ref "H1") (pin "2.3") (pinfunction "2.3_2.3") (pintype "bidirectional"))
    )
    (net (code "115") (name "unconnected-(H1-Pad2.4)") (class "Default")
      (node (ref "H1") (pin "2.4") (pinfunction "2.4_2.4") (pintype "bidirectional"))
    )
    (net (code "116") (name "unconnected-(H1-Pad2.5)") (class "Default")
      (node (ref "H1") (pin "2.5") (pinfunction "2.5_2.5") (pintype "bidirectional"))
    )
    (net (code "117") (name "unconnected-(H1-Pad2.6)") (class "Default")
      (node (ref "H1") (pin "2.6") (pinfunction "2.6_2.6") (pintype "bidirectional"))
    )
    (net (code "118") (name "unconnected-(H1-Pad2.8)") (class "Default")
      (node (ref "H1") (pin "2.8") (pinfunction "2.8_2.8") (pintype "bidirectional"))
    )
    (net (code "119") (name "unconnected-(H1-Pad2.9)") (class "Default")
      (node (ref "H1") (pin "2.9") (pinfunction "2.9_2.9") (pintype "bidirectional"))
    )
    (net (code "120") (name "unconnected-(H1-Pad2.10)") (class "Default")
      (node (ref "H1") (pin "2.10") (pinfunction "2.10_2.10") (pintype "bidirectional"))
    )
    (net (code "121") (name "unconnected-(H1-Pad2.11)") (class "Default")
      (node (ref "H1") (pin "2.11") (pinfunction "2.11_2.11") (pintype "bidirectional"))
    )
    (net (code "122") (name "unconnected-(H1-Pad2.12)") (class "Default")
      (node (ref "H1") (pin "2.12") (pinfunction "2.12_2.12") (pintype "bidirectional"))
    )
    (net (code "123") (name "unconnected-(H1-Pad2.13)") (class "Default")
      (node (ref "H1") (pin "2.13") (pinfunction "2.13_2.13") (pintype "bidirectional"))
    )
    (net (code "124") (name "unconnected-(H1-Pad2.15)") (class "Default")
      (node (ref "H1") (pin "2.15") (pinfunction "2.15_2.15") (pintype "bidirectional"))
    )
    (net (code "125") (name "unconnected-(H1-Pad2.16)") (class "Default")
      (node (ref "H1") (pin "2.16") (pinfunction "2.16_2.16") (pintype "bidirectional"))
    )
    (net (code "126") (name "unconnected-(H1-Pad2.18)") (class "Default")
      (node (ref "H1") (pin "2.18") (pinfunction "2.18_2.18") (pintype "bidirectional"))
    )
    (net (code "127") (name "unconnected-(H1-Pad2.19)") (class "Default")
      (node (ref "H1") (pin "2.19") (pinfunction "2.19_2.19") (pintype "bidirectional"))
    )
    (net (code "128") (name "unconnected-(H1-Pad2.20)") (class "Default")
      (node (ref "H1") (pin "2.20") (pinfunction "2.20_2.20") (pintype "bidirectional"))
    )
    (net (code "129") (name "unconnected-(H1-Pad2.23)") (class "Default")
      (node (ref "H1") (pin "2.23") (pinfunction "2.23_2.23") (pintype "bidirectional"))
    )
    (net (code "130") (name "unconnected-(H1-Pad2.24)") (class "Default")
      (node (ref "H1") (pin "2.24") (pinfunction "2.24_2.24") (pintype "bidirectional"))
    )
    (net (code "131") (name "unconnected-(H1-Pad2.31)") (class "Default")
      (node (ref "H1") (pin "2.31") (pinfunction "2.31_2.31") (pintype "bidirectional"))
    )
    (net (code "132") (name "unconnected-(H1-Pad2.33)") (class "Default")
      (node (ref "H1") (pin "2.33") (pinfunction "2.33_2.33") (pintype "bidirectional"))
    )
    (net (code "133") (name "unconnected-(H1-Pad2.34)") (class "Default")
      (node (ref "H1") (pin "2.34") (pinfunction "2.34_2.34") (pintype "bidirectional"))
    )
    (net (code "134") (name "unconnected-(H1-Pad2.35)") (class "Default")
      (node (ref "H1") (pin "2.35") (pinfunction "2.35_2.35") (pintype "bidirectional"))
    )
    (net (code "135") (name "unconnected-(H1-Pad2.36)") (class "Default")
      (node (ref "H1") (pin "2.36") (pinfunction "2.36_2.36") (pintype "bidirectional"))
    )
    (net (code "136") (name "unconnected-(H1-Pad2.37)") (class "Default")
      (node (ref "H1") (pin "2.37") (pinfunction "2.37_2.37") (pintype "bidirectional"))
    )
    (net (code "137") (name "unconnected-(H1-Pad2.38)") (class "Default")
      (node (ref "H1") (pin "2.38") (pinfunction "2.38_2.38") (pintype "bidirectional"))
    )
    (net (code "138") (name "unconnected-(H1-Pad2.39)") (class "Default")
      (node (ref "H1") (pin "2.39") (pinfunction "2.39_2.39") (pintype "bidirectional"))
    )
    (net (code "139") (name "unconnected-(H1-Pad2.40)") (class "Default")
      (node (ref "H1") (pin "2.40") (pinfunction "2.40_2.40") (pintype "bidirectional"))
    )
    (net (code "140") (name "unconnected-(H1-Pad2.41)") (class "Default")
      (node (ref "H1") (pin "2.41") (pinfunction "2.41_2.41") (pintype "bidirectional"))
    )
    (net (code "141") (name "unconnected-(H1-Pad2.42)") (class "Default")
      (node (ref "H1") (pin "2.42") (pinfunction "2.42_2.42") (pintype "bidirectional"))
    )
    (net (code "142") (name "unconnected-(H1-Pad2.43)") (class "Default")
      (node (ref "H1") (pin "2.43") (pinfunction "2.43_2.43") (pintype "bidirectional"))
    )
    (net (code "143") (name "unconnected-(H1-Pad2.44)") (class "Default")
      (node (ref "H1") (pin "2.44") (pinfunction "2.44_2.44") (pintype "bidirectional"))
    )
    (net (code "144") (name "unconnected-(H1-Pad2.45)") (class "Default")
      (node (ref "H1") (pin "2.45") (pinfunction "2.45_2.45") (pintype "bidirectional"))
    )
    (net (code "145") (name "unconnected-(H1-Pad2.46)") (class "Default")
      (node (ref "H1") (pin "2.46") (pinfunction "2.46_2.46") (pintype "bidirectional"))
    )
    (net (code "146") (name "unconnected-(H1-Pad2.49)") (class "Default")
      (node (ref "H1") (pin "2.49") (pinfunction "2.49_2.49") (pintype "bidirectional"))
    )
    (net (code "147") (name "unconnected-(H1-Pad2.50)") (class "Default")
      (node (ref "H1") (pin "2.50") (pinfunction "2.50_2.50") (pintype "bidirectional"))
    )
    (net (code "148") (name "unconnected-(H1-Pad2.51)") (class "Default")
      (node (ref "H1") (pin "2.51") (pinfunction "2.51_2.51") (pintype "bidirectional"))
    )
    (net (code "149") (name "unconnected-(H1-Pad2.52)") (class "Default")
      (node (ref "H1") (pin "2.52") (pinfunction "2.52_2.52") (pintype "bidirectional"))
    )
    (net (code "150") (name "unconnected-(H1-PadP$1)") (class "Default")
      (node (ref "H1") (pin "P$1") (pinfunction "P$1_P$1") (pintype "bidirectional"))
    )
    (net (code "151") (name "unconnected-(H1-PadP$2)") (class "Default")
      (node (ref "H1") (pin "P$2") (pinfunction "P$2_P$2") (pintype "bidirectional"))
    )
    (net (code "152") (name "unconnected-(H1-PadP$3)") (class "Default")
      (node (ref "H1") (pin "P$3") (pinfunction "P$3_P$3") (pintype "bidirectional"))
    )
    (net (code "153") (name "unconnected-(U$1-Pad9-OUT1C)") (class "Default")
      (node (ref "U$1") (pin "9-OUT1C") (pinfunction "9-OUT1C_9-OUT1C") (pintype "bidirectional"))
    )
    (net (code "154") (name "unconnected-(U$1-Pad30-CRX3)") (class "Default")
      (node (ref "U$1") (pin "30-CRX3") (pinfunction "30-CRX3_30-CRX3") (pintype "bidirectional"))
    )
    (net (code "155") (name "unconnected-(U$1-Pad31-CTX3)") (class "Default")
      (node (ref "U$1") (pin "31-CTX3") (pinfunction "31-CTX3_31-CTX3") (pintype "bidirectional"))
    )
    (net (code "156") (name "unconnected-(U$1-Pad32-OUT1B)") (class "Default")
      (node (ref "U$1") (pin "32-OUT1B") (pinfunction "32-OUT1B_32-OUT1B") (pintype "bidirectional"))
    )
    (net (code "157") (name "unconnected-(U$1-Pad37-PWM)") (class "Default")
      (node (ref "U$1") (pin "37-PWM") (pinfunction "37-PWM_37-PWM") (pintype "bidirectional"))
    )
    (net (code "158") (name "unconnected-(U$1-Pad40-A16{slash}CS1)") (class "Default")
      (node (ref "U$1") (pin "40-A16/CS1") (pinfunction "40-A16/CS1_40-A16/CS1") (pintype "bidirectional"))
    )
    (net (code "159") (name "unconnected-(U$1-PadON{slash}OFF)") (class "Default")
      (node (ref "U$1") (pin "ON/OFF") (pinfunction "ON/OFF_ON/OFF") (pintype "bidirectional"))
    )
    (net (code "160") (name "unconnected-(U1-NC-Pad7)") (class "Default")
      (node (ref "U1") (pin "7") (pinfunction "NC_7") (pintype "no_connect"))
    )
    (net (code "161") (name "unconnected-(U1-NC_2-Pad2)") (class "Default")
      (node (ref "U1") (pin "2") (pinfunction "NC_2_2") (pintype "no_connect"))
    )
    (net (code "162") (name "unconnected-(U1-NC_3-Pad3)") (class "Default")
      (node (ref "U1") (pin "3") (pinfunction "NC_3_3") (pintype "no_connect"))
    )
    (net (code "163") (name "unconnected-(U1-NC_4-Pad6)") (class "Default")
      (node (ref "U1") (pin "6") (pinfunction "NC_4_6") (pintype "no_connect"))
    )
    (net (code "164") (name "unconnected-(U3-DIO1-Pad11)") (class "Default")
      (node (ref "U3") (pin "11") (pinfunction "DIO1_11") (pintype "bidirectional"))
    )
    (net (code "165") (name "unconnected-(U3-DIO2-Pad12)") (class "Default")
      (node (ref "U3") (pin "12") (pinfunction "DIO2_12") (pintype "bidirectional"))
    )
    (net (code "166") (name "unconnected-(U3-DIO3-Pad13)") (class "Default")
      (node (ref "U3") (pin "13") (pinfunction "DIO3_13") (pintype "bidirectional"))
    )
    (net (code "167") (name "unconnected-(U3-DIO4-Pad14)") (class "Default")
      (node (ref "U3") (pin "14") (pinfunction "DIO4_14") (pintype "bidirectional"))
    )
    (net (code "168") (name "unconnected-(U3-DIO5-Pad15)") (class "Default")
      (node (ref "U3") (pin "15") (pinfunction "DIO5_15") (pintype "bidirectional"))
    )
    (net (code "169") (name "unconnected-(U3-NC-Pad1)") (class "Default")
      (node (ref "U3") (pin "1") (pinfunction "NC_1") (pintype "bidirectional"))
    )
    (net (code "170") (name "unconnected-(U5-Pad1)") (class "Default")
      (node (ref "U5") (pin "1") (pinfunction "1_1") (pintype "passive"))
    )
    (net (code "171") (name "unconnected-(U6-P$3-Pad3)") (class "Default")
      (node (ref "U6") (pin "3") (pinfunction "P$3_3") (pintype "bidirectional"))
    )
    (net (code "172") (name "unconnected-(U6-P$4-Pad4)") (class "Default")
      (node (ref "U6") (pin "4") (pinfunction "P$4_4") (pintype "bidirectional"))
    )
    (net (code "173") (name "unconnected-(U6-P$5-Pad5)") (class "Default")
      (node (ref "U6") (pin "5") (pinfunction "P$5_5") (pintype "bidirectional"))
    )
    (net (code "174") (name "unconnected-(U6-P$6-Pad6)") (class "Default")
      (node (ref "U6") (pin "6") (pinfunction "P$6_6") (pintype "bidirectional"))
    )
    (net (code "175") (name "unconnected-(U6-P$8-Pad8)") (class "Default")
      (node (ref "U6") (pin "8") (pinfunction "P$8_8") (pintype "bidirectional"))
    )
    (net (code "176") (name "unconnected-(U6-P$12-Pad12)") (class "Default")
      (node (ref "U6") (pin "12") (pinfunction "P$12_12") (pintype "bidirectional"))
    )
    (net (code "177") (name "unconnected-(U6-P$13-Pad13)") (class "Default")
      (node (ref "U6") (pin "13") (pinfunction "P$13_13") (pintype "bidirectional"))
    )
    (net (code "178") (name "unconnected-(U6-P$14-Pad14)") (class "Default")
      (node (ref "U6") (pin "14") (pinfunction "P$14_14") (pintype "bidirectional"))
    )
    (net (code "179") (name "unconnected-(U6-P$16-Pad16)") (class "Default")
      (node (ref "U6") (pin "16") (pinfunction "P$16_16") (pintype "bidirectional"))
    )
    (net (code "180") (name "unconnected-(U6-P$17-Pad17)") (class "Default")
      (node (ref "U6") (pin "17") (pinfunction "P$17_17") (pintype "bidirectional"))
    )
    (net (code "181") (name "unconnected-(U6-P$20-Pad20)") (class "Default")
      (node (ref "U6") (pin "20") (pinfunction "P$20_20") (pintype "bidirectional"))
    )
    (net (code "182") (name "unconnected-(U6-P$23-Pad23)") (class "Default")
      (node (ref "U6") (pin "23") (pinfunction "P$23_23") (pintype "bidirectional"))
    )
    (net (code "183") (name "unconnected-(U6-P$26-Pad26)") (class "Default")
      (node (ref "U6") (pin "26") (pinfunction "P$26_26") (pintype "bidirectional"))
    )
    (net (code "184") (name "unconnected-(U6-P$30-Pad30)") (class "Default")
      (node (ref "U6") (pin "30") (pinfunction "P$30_30") (pintype "bidirectional"))
    )
    (net (code "185") (name "unconnected-(U6-P$34-Pad34)") (class "Default")
      (node (ref "U6") (pin "34") (pinfunction "P$34_34") (pintype "bidirectional"))
    )
    (net (code "186") (name "unconnected-(U6-P$35-Pad35)") (class "Default")
      (node (ref "U6") (pin "35") (pinfunction "P$35_35") (pintype "bidirectional"))
    )
    (net (code "187") (name "unconnected-(U6-P$36-Pad36)") (class "Default")
      (node (ref "U6") (pin "36") (pinfunction "P$36_36") (pintype "bidirectional"))
    )
    (net (code "188") (name "unconnected-(U6-P$37-Pad37)") (class "Default")
      (node (ref "U6") (pin "37") (pinfunction "P$37_37") (pintype "bidirectional"))
    )
    (net (code "189") (name "unconnected-(U6-P$38-Pad38)") (class "Default")
      (node (ref "U6") (pin "38") (pinfunction "P$38_38") (pintype "bidirectional"))
    )
    (net (code "190") (name "unconnected-(U6-P$39-Pad39)") (class "Default")
      (node (ref "U6") (pin "39") (pinfunction "P$39_39") (pintype "bidirectional"))
    )
    (net (code "191") (name "unconnected-(U6-P$40-Pad40)") (class "Default")
      (node (ref "U6") (pin "40") (pinfunction "P$40_40") (pintype "bidirectional"))
    )
    (net (code "192") (name "unconnected-(U6-P$41-Pad41)") (class "Default")
      (node (ref "U6") (pin "41") (pinfunction "P$41_41") (pintype "bidirectional"))
    )
    (net (code "193") (name "unconnected-(U6-P$43-Pad43)") (class "Default")
      (node (ref "U6") (pin "43") (pinfunction "P$43_43") (pintype "bidirectional"))
    )
    (net (code "194") (name "unconnected-(U6-P$45-Pad45)") (class "Default")
      (node (ref "U6") (pin "45") (pinfunction "P$45_45") (pintype "bidirectional"))
    )
    (net (code "195") (name "unconnected-(U6-P$46-Pad46)") (class "Default")
      (node (ref "U6") (pin "46") (pinfunction "P$46_46") (pintype "bidirectional"))
    )
    (net (code "196") (name "unconnected-(U6-P$47-Pad47)") (class "Default")
      (node (ref "U6") (pin "47") (pinfunction "P$47_47") (pintype "bidirectional"))
    )
    (net (code "197") (name "unconnected-(U6-P$48-Pad48)") (class "Default")
      (node (ref "U6") (pin "48") (pinfunction "P$48_48") (pintype "bidirectional"))
    )
    (net (code "198") (name "unconnected-(U6-P$49-Pad49)") (class "Default")
      (node (ref "U6") (pin "49") (pinfunction "P$49_49") (pintype "bidirectional"))
    )
    (net (code "199") (name "unconnected-(U6-P$50-Pad50)") (class "Default")
      (node (ref "U6") (pin "50") (pinfunction "P$50_50") (pintype "bidirectional"))
    )
    (net (code "200") (name "unconnected-(U6-P$51-Pad51)") (class "Default")
      (node (ref "U6") (pin "51") (pinfunction "P$51_51") (pintype "bidirectional"))
    )
    (net (code "201") (name "unconnected-(U6-P$52-Pad52)") (class "Default")
      (node (ref "U6") (pin "52") (pinfunction "P$52_52") (pintype "bidirectional"))
    )
    (net (code "202") (name "unconnected-(U6-P$53-Pad53)") (class "Default")
      (node (ref "U6") (pin "53") (pinfunction "P$53_53") (pintype "bidirectional"))
    )
    (net (code "203") (name "unconnected-(U6-P$54-Pad54)") (class "Default")
      (node (ref "U6") (pin "54") (pinfunction "P$54_54") (pintype "bidirectional"))
    )
    (net (code "204") (name "unconnected-(U6-P$55-Pad55)") (class "Default")
      (node (ref "U6") (pin "55") (pinfunction "P$55_55") (pintype "bidirectional"))
    )
    (net (code "205") (name "unconnected-(U6-P$56-Pad56)") (class "Default")
      (node (ref "U6") (pin "56") (pinfunction "P$56_56") (pintype "bidirectional"))
    )
    (net (code "206") (name "unconnected-(U6-P$57-Pad57)") (class "Default")
      (node (ref "U6") (pin "57") (pinfunction "P$57_57") (pintype "bidirectional"))
    )
    (net (code "207") (name "unconnected-(U6-P$59-Pad59)") (class "Default")
      (node (ref "U6") (pin "59") (pinfunction "P$59_59") (pintype "bidirectional"))
    )
    (net (code "208") (name "unconnected-(U6-P$60-Pad60)") (class "Default")
      (node (ref "U6") (pin "60") (pinfunction "P$60_60") (pintype "bidirectional"))
    )
    (net (code "209") (name "unconnected-(U6-P$61-Pad61)") (class "Default")
      (node (ref "U6") (pin "61") (pinfunction "P$61_61") (pintype "bidirectional"))
    )
    (net (code "210") (name "unconnected-(U6-P$62-Pad62)") (class "Default")
      (node (ref "U6") (pin "62") (pinfunction "P$62_62") (pintype "bidirectional"))
    )
    (net (code "211") (name "unconnected-(U6-P$63-Pad63)") (class "Default")
      (node (ref "U6") (pin "63") (pinfunction "P$63_63") (pintype "bidirectional"))
    )
    (net (code "212") (name "unconnected-(U6-P$65-Pad65)") (class "Default")
      (node (ref "U6") (pin "65") (pinfunction "P$65_65") (pintype "bidirectional"))
    )
    (net (code "213") (name "unconnected-(U6-P$66-Pad66)") (class "Default")
      (node (ref "U6") (pin "66") (pinfunction "P$66_66") (pintype "bidirectional"))
    )
    (net (code "214") (name "unconnected-(U6-P$67-Pad67)") (class "Default")
      (node (ref "U6") (pin "67") (pinfunction "P$67_67") (pintype "bidirectional"))
    )
    (net (code "215") (name "unconnected-(U6-P$68-Pad68)") (class "Default")
      (node (ref "U6") (pin "68") (pinfunction "P$68_68") (pintype "bidirectional"))
    )
    (net (code "216") (name "unconnected-(U6-P$69-Pad69)") (class "Default")
      (node (ref "U6") (pin "69") (pinfunction "P$69_69") (pintype "bidirectional"))
    )
    (net (code "217") (name "unconnected-(X1-P$1-Pad1)") (class "Default")
      (node (ref "X1") (pin "1") (pinfunction "P$1_1") (pintype "bidirectional"))
    )
    (net (code "218") (name "unconnected-(X1-P$4-Pad4)") (class "Default")
      (node (ref "X1") (pin "4") (pinfunction "P$4_4") (pintype "bidirectional"))
    )
    (net (code "219") (name "unconnected-(X1-P$6-Pad6)") (class "Default")
      (node (ref "X1") (pin "6") (pinfunction "P$6_6") (pintype "bidirectional"))
    )
    (net (code "220") (name "unconnected-(X1-P$7-Pad7)") (class "Default")
      (node (ref "X1") (pin "7") (pinfunction "P$7_7") (pintype "bidirectional"))
    )
    (net (code "221") (name "unconnected-(X1-P$8-Pad8)") (class "Default")
      (node (ref "X1") (pin "8") (pinfunction "P$8_8") (pintype "bidirectional"))
    )
    (net (code "222") (name "unconnected-(X1-P$9-Pad9)") (class "Default")
      (node (ref "X1") (pin "9") (pinfunction "P$9_9") (pintype "bidirectional"))
    )
    (net (code "223") (name "unconnected-(X1-P$10-Pad10)") (class "Default")
      (node (ref "X1") (pin "10") (pinfunction "P$10_10") (pintype "bidirectional"))
    )
    (net (code "224") (name "unconnected-(X1-P$12-Pad12)") (class "Default")
      (node (ref "X1") (pin "12") (pinfunction "P$12_12") (pintype "bidirectional"))
    )
    (net (code "225") (name "unconnected-(X1-P$14-Pad14)") (class "Default")
      (node (ref "X1") (pin "14") (pinfunction "P$14_14") (pintype "bidirectional"))
    )
    (net (code "226") (name "unconnected-(X1-P$17-Pad17)") (class "Default")
      (node (ref "X1") (pin "17") (pinfunction "P$17_17") (pintype "bidirectional"))
    )
    (net (code "227") (name "unconnected-(X1-P$20-Pad20)") (class "Default")
      (node (ref "X1") (pin "20") (pinfunction "P$20_20") (pintype "bidirectional"))
    )
    (net (code "228") (name "unconnected-(X1-P$25-Pad25)") (class "Default")
      (node (ref "X1") (pin "25") (pinfunction "P$25_25") (pintype "bidirectional"))
    )
    (net (code "229") (name "unconnected-(X1-P$27-Pad27)") (class "Default")
      (node (ref "X1") (pin "27") (pinfunction "P$27_27") (pintype "bidirectional"))
    )
    (net (code "230") (name "unconnected-(X1-P$28-Pad28)") (class "Default")
      (node (ref "X1") (pin "28") (pinfunction "P$28_28") (pintype "bidirectional"))
    )
    (net (code "231") (name "unconnected-(X1-P$29-Pad29)") (class "Default")
      (node (ref "X1") (pin "29") (pinfunction "P$29_29") (pintype "bidirectional"))
    )
    (net (code "232") (name "unconnected-(X1-P$30-Pad30)") (class "Default")
      (node (ref "X1") (pin "30") (pinfunction "P$30_30") (pintype "bidirectional"))
    )
    (net (code "233") (name "unconnected-(X1-P$31-Pad31)") (class "Default")
      (node (ref "X1") (pin "31") (pinfunction "P$31_31") (pintype "bidirectional"))
    )
    (net (code "234") (name "unconnected-(X1-P$32-Pad32)") (class "Default")
      (node (ref "X1") (pin "32") (pinfunction "P$32_32") (pintype "bidirectional"))
    )
    (net (code "235") (name "unconnected-(X1-P$33-Pad33)") (class "Default")
      (node (ref "X1") (pin "33") (pinfunction "P$33_33") (pintype "bidirectional"))
    )
    (net (code "236") (name "unconnected-(X1-P$34-Pad34)") (class "Default")
      (node (ref "X1") (pin "34") (pinfunction "P$34_34") (pintype "bidirectional"))
    )
    (net (code "237") (name "unconnected-(X1-P$35-Pad35)") (class "Default")
      (node (ref "X1") (pin "35") (pinfunction "P$35_35") (pintype "bidirectional"))
    )
    (net (code "238") (name "unconnected-(X1-P$36-Pad36)") (class "Default")
      (node (ref "X1") (pin "36") (pinfunction "P$36_36") (pintype "bidirectional"))
    )
    (net (code "239") (name "unconnected-(X1-P$37-Pad37)") (class "Default")
      (node (ref "X1") (pin "37") (pinfunction "P$37_37") (pintype "bidirectional"))
    )
    (net (code "240") (name "unconnected-(X1-P$38-Pad38)") (class "Default")
      (node (ref "X1") (pin "38") (pinfunction "P$38_38") (pintype "bidirectional"))
    )
    (net (code "241") (name "unconnected-(X1-P$40-Pad40)") (class "Default")
      (node (ref "X1") (pin "40") (pinfunction "P$40_40") (pintype "bidirectional"))
    )
    (net (code "242") (name "unconnected-(X2-Pad1)") (class "Default")
      (node (ref "X2") (pin "1") (pinfunction "1_1") (pintype "passive"))
    )
    (net (code "243") (name "unconnected-(X2AA-1-Pad33)") (class "Default")
      (node (ref "X2") (pin "33") (pinfunction "1_33") (pintype "passive"))
    )
    (net (code "244") (name "unconnected-(X2AB-1-Pad34)") (class "Default")
      (node (ref "X2") (pin "34") (pinfunction "1_34") (pintype "passive"))
    )
    (net (code "245") (name "unconnected-(X2AC-1-Pad35)") (class "Default")
      (node (ref "X2") (pin "35") (pinfunction "1_35") (pintype "passive"))
    )
    (net (code "246") (name "unconnected-(X2AD-1-Pad36)") (class "Default")
      (node (ref "X2") (pin "36") (pinfunction "1_36") (pintype "passive"))
    )
    (net (code "247") (name "unconnected-(X2AE-1-Pad37)") (class "Default")
      (node (ref "X2") (pin "37") (pinfunction "1_37") (pintype "passive"))
    )
    (net (code "248") (name "unconnected-(X2AF-1-Pad38)") (class "Default")
      (node (ref "X2") (pin "38") (pinfunction "1_38") (pintype "passive"))
    )
    (net (code "249") (name "unconnected-(X2AG-1-Pad39)") (class "Default")
      (node (ref "X2") (pin "39") (pinfunction "1_39") (pintype "passive"))
    )
    (net (code "250") (name "unconnected-(X2AH-1-Pad4)") (class "Default")
      (node (ref "X2") (pin "4") (pinfunction "1_4") (pintype "passive"))
    )
    (net (code "251") (name "unconnected-(X2AI-1-Pad40)") (class "Default")
      (node (ref "X2") (pin "40") (pinfunction "1_40") (pintype "passive"))
    )
    (net (code "252") (name "unconnected-(X2AJ-1-Pad5)") (class "Default")
      (node (ref "X2") (pin "5") (pinfunction "1_5") (pintype "passive"))
    )
    (net (code "253") (name "unconnected-(X2AK-1-Pad6)") (class "Default")
      (node (ref "X2") (pin "6") (pinfunction "1_6") (pintype "passive"))
    )
    (net (code "254") (name "unconnected-(X2AL-1-Pad7)") (class "Default")
      (node (ref "X2") (pin "7") (pinfunction "1_7") (pintype "passive"))
    )
    (net (code "255") (name "unconnected-(X2AM-1-Pad8)") (class "Default")
      (node (ref "X2") (pin "8") (pinfunction "1_8") (pintype "passive"))
    )
    (net (code "256") (name "unconnected-(X2AN-1-Pad9)") (class "Default")
      (node (ref "X2") (pin "9") (pinfunction "1_9") (pintype "passive"))
    )
    (net (code "257") (name "unconnected-(X2B-1-Pad10)") (class "Default")
      (node (ref "X2") (pin "10") (pinfunction "1_10") (pintype "passive"))
    )
    (net (code "258") (name "unconnected-(X2C-1-Pad11)") (class "Default")
      (node (ref "X2") (pin "11") (pinfunction "1_11") (pintype "passive"))
    )
    (net (code "259") (name "unconnected-(X2D-1-Pad12)") (class "Default")
      (node (ref "X2") (pin "12") (pinfunction "1_12") (pintype "passive"))
    )
    (net (code "260") (name "unconnected-(X2E-1-Pad13)") (class "Default")
      (node (ref "X2") (pin "13") (pinfunction "1_13") (pintype "passive"))
    )
    (net (code "261") (name "unconnected-(X2F-1-Pad14)") (class "Default")
      (node (ref "X2") (pin "14") (pinfunction "1_14") (pintype "passive"))
    )
    (net (code "262") (name "unconnected-(X2G-1-Pad15)") (class "Default")
      (node (ref "X2") (pin "15") (pinfunction "1_15") (pintype "passive"))
    )
    (net (code "263") (name "unconnected-(X2H-1-Pad16)") (class "Default")
      (node (ref "X2") (pin "16") (pinfunction "1_16") (pintype "passive"))
    )
    (net (code "264") (name "unconnected-(X2I-1-Pad17)") (class "Default")
      (node (ref "X2") (pin "17") (pinfunction "1_17") (pintype "passive"))
    )
    (net (code "265") (name "unconnected-(X2J-1-Pad18)") (class "Default")
      (node (ref "X2") (pin "18") (pinfunction "1_18") (pintype "passive"))
    )
    (net (code "266") (name "unconnected-(X2K-1-Pad19)") (class "Default")
      (node (ref "X2") (pin "19") (pinfunction "1_19") (pintype "passive"))
    )
    (net (code "267") (name "unconnected-(X2L-1-Pad2)") (class "Default")
      (node (ref "X2") (pin "2") (pinfunction "1_2") (pintype "passive"))
    )
    (net (code "268") (name "unconnected-(X2M-1-Pad20)") (class "Default")
      (node (ref "X2") (pin "20") (pinfunction "1_20") (pintype "passive"))
    )
    (net (code "269") (name "unconnected-(X2N-1-Pad21)") (class "Default")
      (node (ref "X2") (pin "21") (pinfunction "1_21") (pintype "passive"))
    )
    (net (code "270") (name "unconnected-(X2O-1-Pad22)") (class "Default")
      (node (ref "X2") (pin "22") (pinfunction "1_22") (pintype "passive"))
    )
    (net (code "271") (name "unconnected-(X2P-1-Pad23)") (class "Default")
      (node (ref "X2") (pin "23") (pinfunction "1_23") (pintype "passive"))
    )
    (net (code "272") (name "unconnected-(X2Q-1-Pad24)") (class "Default")
      (node (ref "X2") (pin "24") (pinfunction "1_24") (pintype "passive"))
    )
    (net (code "273") (name "unconnected-(X2R-1-Pad25)") (class "Default")
      (node (ref "X2") (pin "25") (pinfunction "1_25") (pintype "passive"))
    )
    (net (code "274") (name "unconnected-(X2S-1-Pad26)") (class "Default")
      (node (ref "X2") (pin "26") (pinfunction "1_26") (pintype "passive"))
    )
    (net (code "275") (name "unconnected-(X2T-1-Pad27)") (class "Default")
      (node (ref "X2") (pin "27") (pinfunction "1_27") (pintype "passive"))
    )
    (net (code "276") (name "unconnected-(X2U-1-Pad28)") (class "Default")
      (node (ref "X2") (pin "28") (pinfunction "1_28") (pintype "passive"))
    )
    (net (code "277") (name "unconnected-(X2V-1-Pad29)") (class "Default")
      (node (ref "X2") (pin "29") (pinfunction "1_29") (pintype "passive"))
    )
    (net (code "278") (name "unconnected-(X2W-1-Pad3)") (class "Default")
      (node (ref "X2") (pin "3") (pinfunction "1_3") (pintype "passive"))
    )
    (net (code "279") (name "unconnected-(X2X-1-Pad30)") (class "Default")
      (node (ref "X2") (pin "30") (pinfunction "1_30") (pintype "passive"))
    )
    (net (code "280") (name "unconnected-(X2Y-1-Pad31)") (class "Default")
      (node (ref "X2") (pin "31") (pinfunction "1_31") (pintype "passive"))
    )
    (net (code "281") (name "unconnected-(X2Z-1-Pad32)") (class "Default")
      (node (ref "X2") (pin "32") (pinfunction "1_32") (pintype "passive"))
    )
  )
)
